# balancer.net
KiCad netlist of a schematic drawn in EAGLE
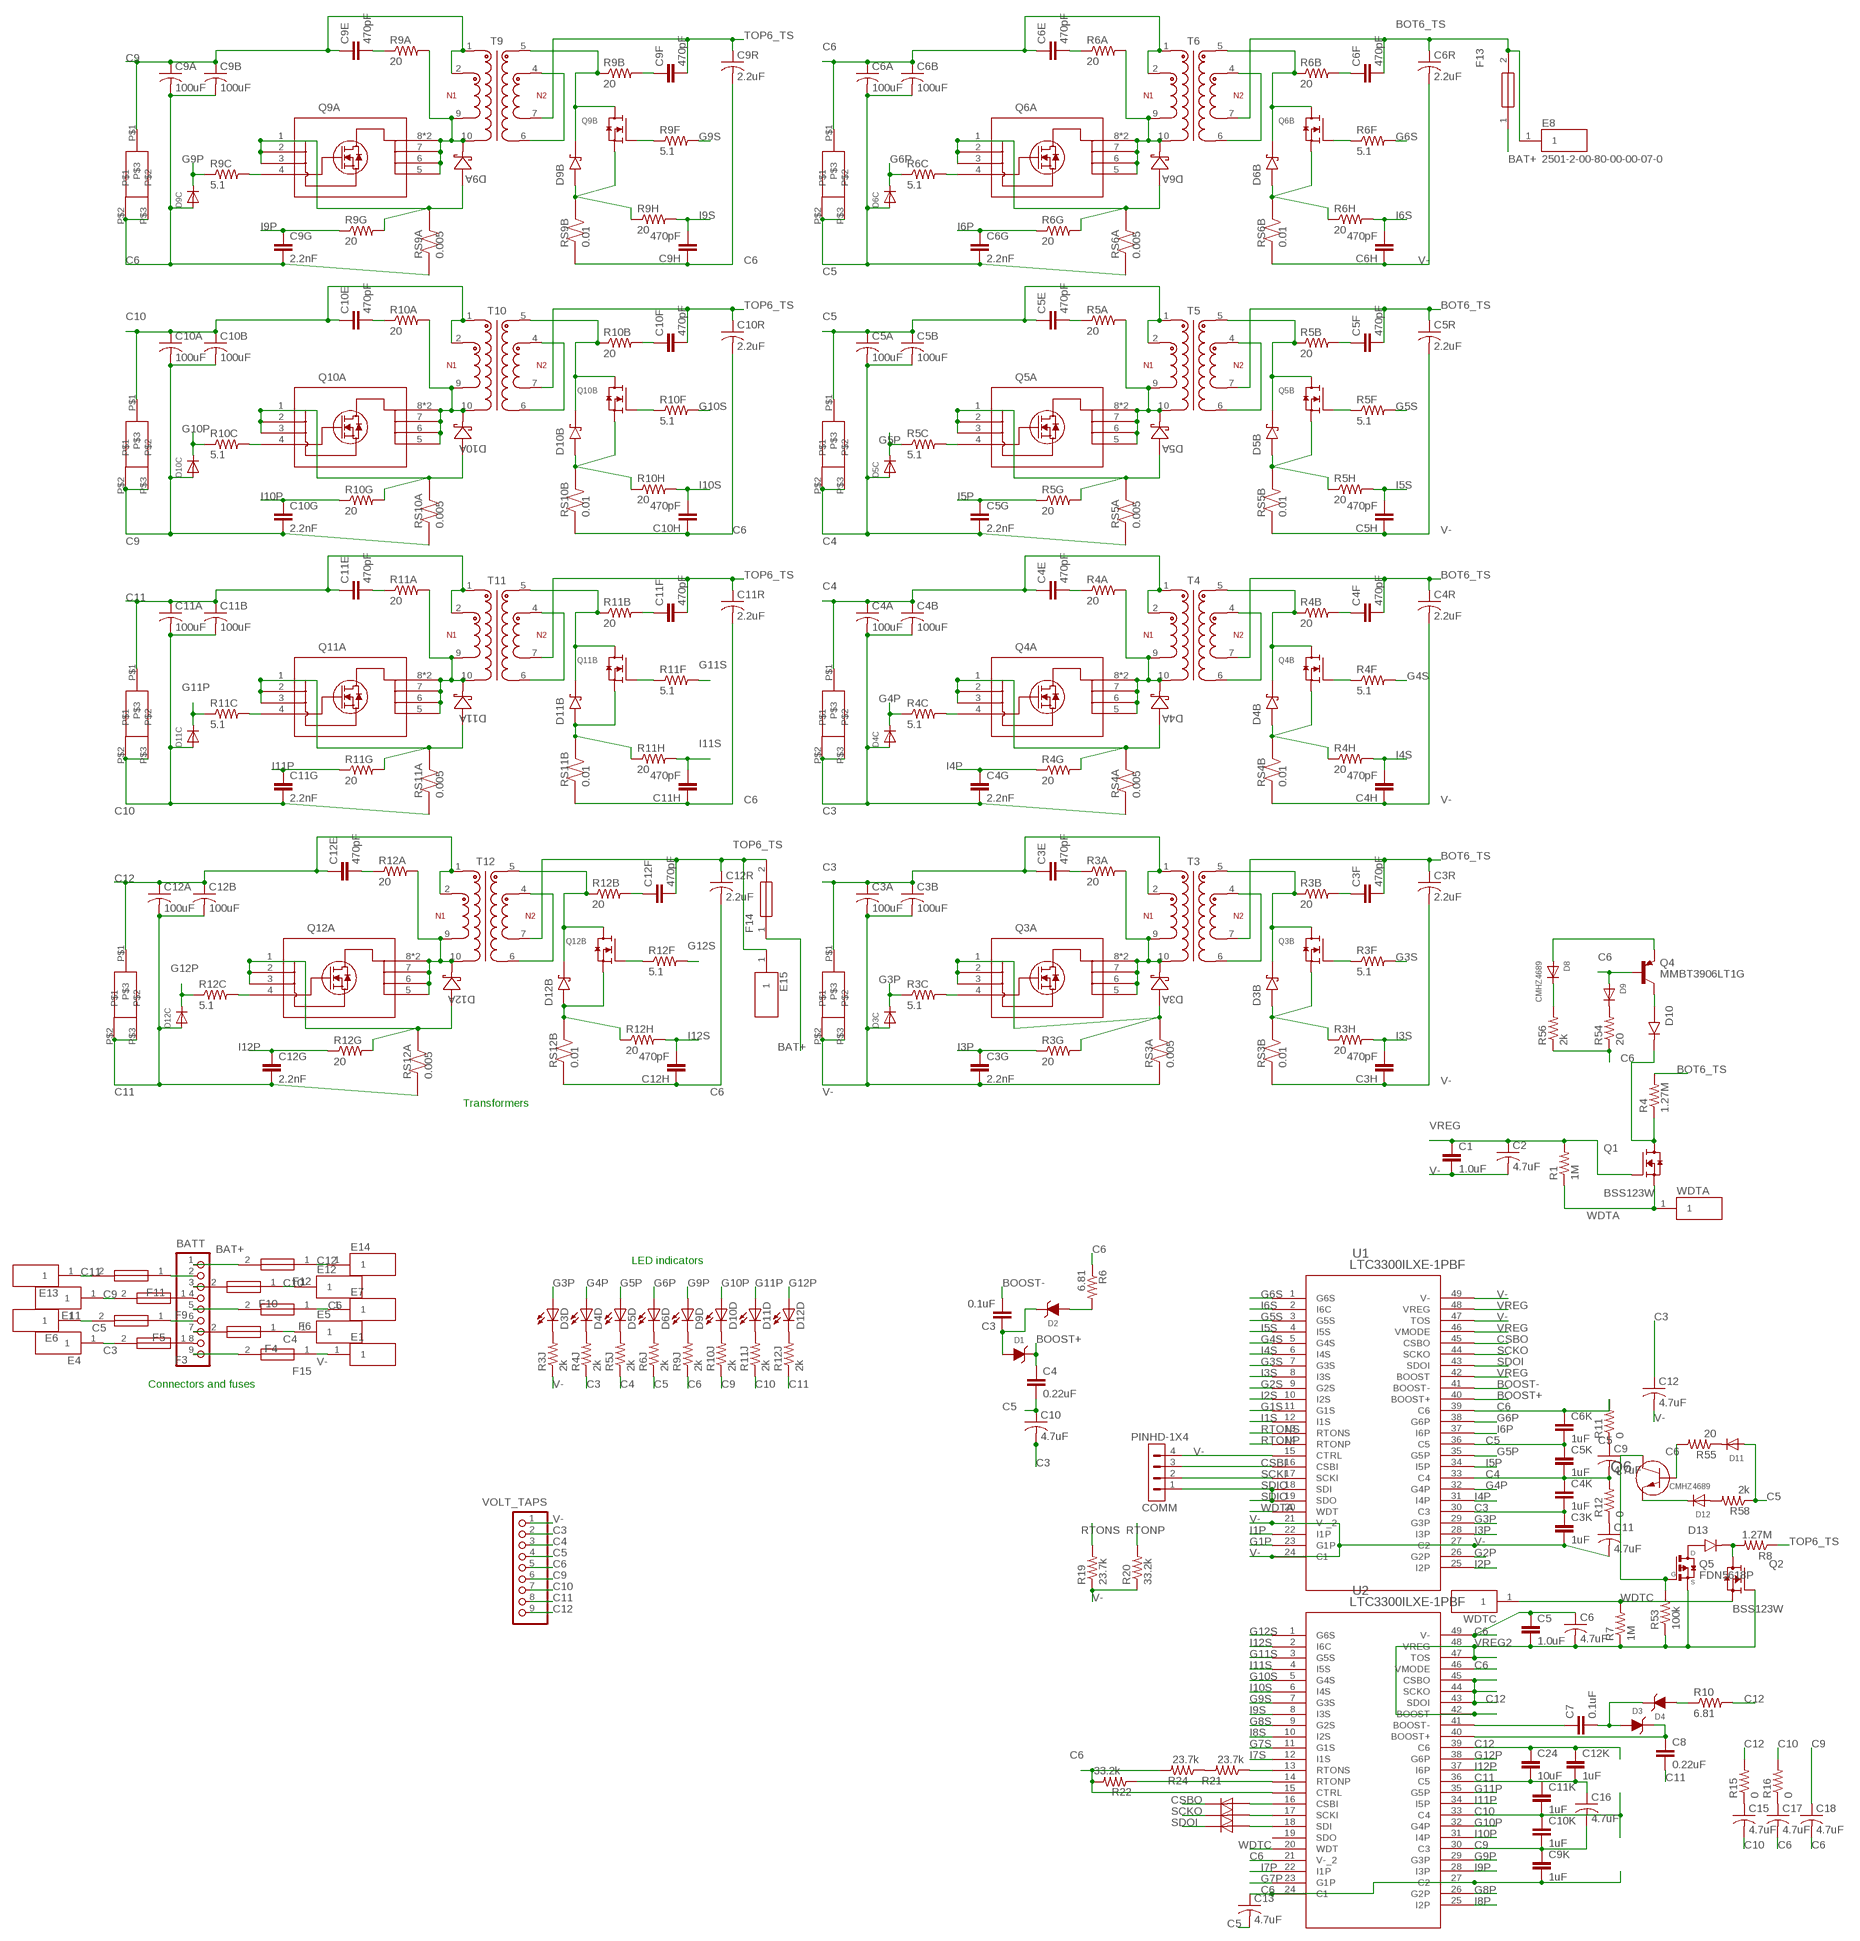
[diagram p0: schematic, sheet 1]

(export (version "E")
  (design (tool "Eeschema 10.0.6"))
  (components
    (comp (ref "BATT")
      (value "B9P-VH")
      (footprint "eagle-import:B9P-VH")
      (libsource (lib "eagle-import") (part "B9P-VH"))
    )
    (comp (ref "C1")
      (value "1.0uF")
      (footprint "eagle-import:0805")
      (libsource (lib "eagle-import") (part "CAP"))
    )
    (comp (ref "C2")
      (value "4.7uF")
      (footprint "eagle-import:C1210")
      (libsource (lib "eagle-import") (part "C-USC1210"))
    )
    (comp (ref "C3")
      (value "0.1uF")
      (footprint "eagle-import:0805")
      (libsource (lib "eagle-import") (part "CAP"))
    )
    (comp (ref "C3A")
      (value "100uF")
      (footprint "eagle-import:C1210")
      (libsource (lib "eagle-import") (part "C-USC1210"))
    )
    (comp (ref "C3B")
      (value "100uF")
      (footprint "eagle-import:C1210")
      (libsource (lib "eagle-import") (part "C-USC1210"))
    )
    (comp (ref "C3E")
      (value "470pF")
      (footprint "eagle-import:0805")
      (libsource (lib "eagle-import") (part "CAP"))
    )
    (comp (ref "C3F")
      (value "470pF")
      (footprint "eagle-import:0805")
      (libsource (lib "eagle-import") (part "CAP"))
    )
    (comp (ref "C3G")
      (value "2.2nF")
      (footprint "eagle-import:0805")
      (libsource (lib "eagle-import") (part "CAP"))
    )
    (comp (ref "C3H")
      (value "470pF")
      (footprint "eagle-import:0805")
      (libsource (lib "eagle-import") (part "CAP"))
    )
    (comp (ref "C3K")
      (value "1uF")
      (footprint "eagle-import:0805")
      (libsource (lib "eagle-import") (part "CAP"))
    )
    (comp (ref "C3R")
      (value "2.2uF")
      (footprint "eagle-import:C1210")
      (libsource (lib "eagle-import") (part "C-USC1210"))
    )
    (comp (ref "C4")
      (value "0.22uF")
      (footprint "eagle-import:0805")
      (libsource (lib "eagle-import") (part "CAP"))
    )
    (comp (ref "C4A")
      (value "100uF")
      (footprint "eagle-import:C1210")
      (libsource (lib "eagle-import") (part "C-USC1210"))
    )
    (comp (ref "C4B")
      (value "100uF")
      (footprint "eagle-import:C1210")
      (libsource (lib "eagle-import") (part "C-USC1210"))
    )
    (comp (ref "C4E")
      (value "470pF")
      (footprint "eagle-import:0805")
      (libsource (lib "eagle-import") (part "CAP"))
    )
    (comp (ref "C4F")
      (value "470pF")
      (footprint "eagle-import:0805")
      (libsource (lib "eagle-import") (part "CAP"))
    )
    (comp (ref "C4G")
      (value "2.2nF")
      (footprint "eagle-import:0805")
      (libsource (lib "eagle-import") (part "CAP"))
    )
    (comp (ref "C4H")
      (value "470pF")
      (footprint "eagle-import:0805")
      (libsource (lib "eagle-import") (part "CAP"))
    )
    (comp (ref "C4K")
      (value "1uF")
      (footprint "eagle-import:0805")
      (libsource (lib "eagle-import") (part "CAP"))
    )
    (comp (ref "C4R")
      (value "2.2uF")
      (footprint "eagle-import:C1210")
      (libsource (lib "eagle-import") (part "C-USC1210"))
    )
    (comp (ref "C5")
      (value "1.0uF")
      (footprint "eagle-import:0805")
      (libsource (lib "eagle-import") (part "CAP"))
    )
    (comp (ref "C5A")
      (value "100uF")
      (footprint "eagle-import:C1210")
      (libsource (lib "eagle-import") (part "C-USC1210"))
    )
    (comp (ref "C5B")
      (value "100uF")
      (footprint "eagle-import:C1210")
      (libsource (lib "eagle-import") (part "C-USC1210"))
    )
    (comp (ref "C5E")
      (value "470pF")
      (footprint "eagle-import:0805")
      (libsource (lib "eagle-import") (part "CAP"))
    )
    (comp (ref "C5F")
      (value "470pF")
      (footprint "eagle-import:0805")
      (libsource (lib "eagle-import") (part "CAP"))
    )
    (comp (ref "C5G")
      (value "2.2nF")
      (footprint "eagle-import:0805")
      (libsource (lib "eagle-import") (part "CAP"))
    )
    (comp (ref "C5H")
      (value "470pF")
      (footprint "eagle-import:0805")
      (libsource (lib "eagle-import") (part "CAP"))
    )
    (comp (ref "C5K")
      (value "1uF")
      (footprint "eagle-import:0805")
      (libsource (lib "eagle-import") (part "CAP"))
    )
    (comp (ref "C5R")
      (value "2.2uF")
      (footprint "eagle-import:C1210")
      (libsource (lib "eagle-import") (part "C-USC1210"))
    )
    (comp (ref "C6")
      (value "4.7uF")
      (footprint "eagle-import:C1210")
      (libsource (lib "eagle-import") (part "C-USC1210"))
    )
    (comp (ref "C6A")
      (value "100uF")
      (footprint "eagle-import:C1210")
      (libsource (lib "eagle-import") (part "C-USC1210"))
    )
    (comp (ref "C6B")
      (value "100uF")
      (footprint "eagle-import:C1210")
      (libsource (lib "eagle-import") (part "C-USC1210"))
    )
    (comp (ref "C6E")
      (value "470pF")
      (footprint "eagle-import:0805")
      (libsource (lib "eagle-import") (part "CAP"))
    )
    (comp (ref "C6F")
      (value "470pF")
      (footprint "eagle-import:0805")
      (libsource (lib "eagle-import") (part "CAP"))
    )
    (comp (ref "C6G")
      (value "2.2nF")
      (footprint "eagle-import:0805")
      (libsource (lib "eagle-import") (part "CAP"))
    )
    (comp (ref "C6H")
      (value "470pF")
      (footprint "eagle-import:0805")
      (libsource (lib "eagle-import") (part "CAP"))
    )
    (comp (ref "C6K")
      (value "1uF")
      (footprint "eagle-import:0805")
      (libsource (lib "eagle-import") (part "CAP"))
    )
    (comp (ref "C6R")
      (value "2.2uF")
      (footprint "eagle-import:C1210")
      (libsource (lib "eagle-import") (part "C-USC1210"))
    )
    (comp (ref "C7")
      (value "0.1uF")
      (footprint "eagle-import:0805")
      (libsource (lib "eagle-import") (part "CAP"))
    )
    (comp (ref "C8")
      (value "0.22uF")
      (footprint "eagle-import:0805")
      (libsource (lib "eagle-import") (part "CAP"))
    )
    (comp (ref "C9")
      (value "4.7uF")
      (footprint "eagle-import:C1210")
      (libsource (lib "eagle-import") (part "C-USC1210"))
    )
    (comp (ref "C9A")
      (value "100uF")
      (footprint "eagle-import:C1210")
      (libsource (lib "eagle-import") (part "C-USC1210"))
    )
    (comp (ref "C9B")
      (value "100uF")
      (footprint "eagle-import:C1210")
      (libsource (lib "eagle-import") (part "C-USC1210"))
    )
    (comp (ref "C9E")
      (value "470pF")
      (footprint "eagle-import:0805")
      (libsource (lib "eagle-import") (part "CAP"))
    )
    (comp (ref "C9F")
      (value "470pF")
      (footprint "eagle-import:0805")
      (libsource (lib "eagle-import") (part "CAP"))
    )
    (comp (ref "C9G")
      (value "2.2nF")
      (footprint "eagle-import:0805")
      (libsource (lib "eagle-import") (part "CAP"))
    )
    (comp (ref "C9H")
      (value "470pF")
      (footprint "eagle-import:0805")
      (libsource (lib "eagle-import") (part "CAP"))
    )
    (comp (ref "C9K")
      (value "1uF")
      (footprint "eagle-import:0805")
      (libsource (lib "eagle-import") (part "CAP"))
    )
    (comp (ref "C9R")
      (value "2.2uF")
      (footprint "eagle-import:C1210")
      (libsource (lib "eagle-import") (part "C-USC1210"))
    )
    (comp (ref "C10")
      (value "4.7uF")
      (footprint "eagle-import:C1210")
      (libsource (lib "eagle-import") (part "C-USC1210"))
    )
    (comp (ref "C10A")
      (value "100uF")
      (footprint "eagle-import:C1210")
      (libsource (lib "eagle-import") (part "C-USC1210"))
    )
    (comp (ref "C10B")
      (value "100uF")
      (footprint "eagle-import:C1210")
      (libsource (lib "eagle-import") (part "C-USC1210"))
    )
    (comp (ref "C10E")
      (value "470pF")
      (footprint "eagle-import:0805")
      (libsource (lib "eagle-import") (part "CAP"))
    )
    (comp (ref "C10F")
      (value "470pF")
      (footprint "eagle-import:0805")
      (libsource (lib "eagle-import") (part "CAP"))
    )
    (comp (ref "C10G")
      (value "2.2nF")
      (footprint "eagle-import:0805")
      (libsource (lib "eagle-import") (part "CAP"))
    )
    (comp (ref "C10H")
      (value "470pF")
      (footprint "eagle-import:0805")
      (libsource (lib "eagle-import") (part "CAP"))
    )
    (comp (ref "C10K")
      (value "1uF")
      (footprint "eagle-import:0805")
      (libsource (lib "eagle-import") (part "CAP"))
    )
    (comp (ref "C10R")
      (value "2.2uF")
      (footprint "eagle-import:C1210")
      (libsource (lib "eagle-import") (part "C-USC1210"))
    )
    (comp (ref "C11")
      (value "4.7uF")
      (footprint "eagle-import:C1210")
      (libsource (lib "eagle-import") (part "C-USC1210"))
    )
    (comp (ref "C11A")
      (value "100uF")
      (footprint "eagle-import:C1210")
      (libsource (lib "eagle-import") (part "C-USC1210"))
    )
    (comp (ref "C11B")
      (value "100uF")
      (footprint "eagle-import:C1210")
      (libsource (lib "eagle-import") (part "C-USC1210"))
    )
    (comp (ref "C11E")
      (value "470pF")
      (footprint "eagle-import:0805")
      (libsource (lib "eagle-import") (part "CAP"))
    )
    (comp (ref "C11F")
      (value "470pF")
      (footprint "eagle-import:0805")
      (libsource (lib "eagle-import") (part "CAP"))
    )
    (comp (ref "C11G")
      (value "2.2nF")
      (footprint "eagle-import:0805")
      (libsource (lib "eagle-import") (part "CAP"))
    )
    (comp (ref "C11H")
      (value "470pF")
      (footprint "eagle-import:0805")
      (libsource (lib "eagle-import") (part "CAP"))
    )
    (comp (ref "C11K")
      (value "1uF")
      (footprint "eagle-import:0805")
      (libsource (lib "eagle-import") (part "CAP"))
    )
    (comp (ref "C11R")
      (value "2.2uF")
      (footprint "eagle-import:C1210")
      (libsource (lib "eagle-import") (part "C-USC1210"))
    )
    (comp (ref "C12")
      (value "4.7uF")
      (footprint "eagle-import:C1210")
      (libsource (lib "eagle-import") (part "C-USC1210"))
    )
    (comp (ref "C12A")
      (value "100uF")
      (footprint "eagle-import:C1210")
      (libsource (lib "eagle-import") (part "C-USC1210"))
    )
    (comp (ref "C12B")
      (value "100uF")
      (footprint "eagle-import:C1210")
      (libsource (lib "eagle-import") (part "C-USC1210"))
    )
    (comp (ref "C12E")
      (value "470pF")
      (footprint "eagle-import:0805")
      (libsource (lib "eagle-import") (part "CAP"))
    )
    (comp (ref "C12F")
      (value "470pF")
      (footprint "eagle-import:0805")
      (libsource (lib "eagle-import") (part "CAP"))
    )
    (comp (ref "C12G")
      (value "2.2nF")
      (footprint "eagle-import:0805")
      (libsource (lib "eagle-import") (part "CAP"))
    )
    (comp (ref "C12H")
      (value "470pF")
      (footprint "eagle-import:0805")
      (libsource (lib "eagle-import") (part "CAP"))
    )
    (comp (ref "C12K")
      (value "1uF")
      (footprint "eagle-import:0805")
      (libsource (lib "eagle-import") (part "CAP"))
    )
    (comp (ref "C12R")
      (value "2.2uF")
      (footprint "eagle-import:C1210")
      (libsource (lib "eagle-import") (part "C-USC1210"))
    )
    (comp (ref "C13")
      (value "4.7uF")
      (footprint "eagle-import:C1210")
      (libsource (lib "eagle-import") (part "C-USC1210"))
    )
    (comp (ref "C15")
      (value "4.7uF")
      (footprint "eagle-import:C1210")
      (libsource (lib "eagle-import") (part "C-USC1210"))
    )
    (comp (ref "C16")
      (value "4.7uF")
      (footprint "eagle-import:C1210")
      (libsource (lib "eagle-import") (part "C-USC1210"))
    )
    (comp (ref "C17")
      (value "4.7uF")
      (footprint "eagle-import:C1210")
      (libsource (lib "eagle-import") (part "C-USC1210"))
    )
    (comp (ref "C18")
      (value "4.7uF")
      (footprint "eagle-import:C1210")
      (libsource (lib "eagle-import") (part "C-USC1210"))
    )
    (comp (ref "C24")
      (value "10uF")
      (footprint "eagle-import:0805")
      (libsource (lib "eagle-import") (part "CAP"))
    )
    (comp (ref "COMM")
      (value "PINHD-1X4")
      (footprint "eagle-import:1X04")
      (libsource (lib "eagle-import") (part "PINHD-1X4"))
    )
    (comp (ref "D1")
      (value "WE-TVSP_DO-214AA_600W_UNI")
      (footprint "eagle-import:WE-TVSP_DO-214AA_UNIDIRECTIONAL")
      (fields (field (name "MF") "Würth Elektronik") (field (name "MP") "824520141"))
      (libsource (lib "eagle-import") (part "WE-TVSP_DO-214AA_600W_UNI"))
    )
    (comp (ref "D2")
      (value "WE-TVSP_DO-214AA_600W_UNI")
      (footprint "eagle-import:WE-TVSP_DO-214AA_UNIDIRECTIONAL")
      (fields (field (name "MF") "Würth Elektronik") (field (name "MP") "824520141"))
      (libsource (lib "eagle-import") (part "WE-TVSP_DO-214AA_600W_UNI"))
    )
    (comp (ref "D3")
      (value "WE-TVSP_DO-214AA_600W_UNI")
      (footprint "eagle-import:WE-TVSP_DO-214AA_UNIDIRECTIONAL")
      (fields (field (name "MF") "Würth Elektronik") (field (name "MP") "824520141"))
      (libsource (lib "eagle-import") (part "WE-TVSP_DO-214AA_600W_UNI"))
    )
    (comp (ref "D3A")
      (value "DFLS260Q-7")
      (footprint "eagle-import:SDO_POWERDI123_DIO")
      (fields (field (name "COPYRIGHT") "Copyright (C) 2026 Ultra Librarian. All rights reserved."))
      (libsource (lib "eagle-import") (part "DFLS260Q-7"))
    )
    (comp (ref "D3B")
      (value "DFLS1100-7")
      (footprint "eagle-import:DIO_DFLS1100-7")
      (fields (field (name "MANUFACTURER") "Diodes Inc."))
      (libsource (lib "eagle-import") (part "DFLS1100-7"))
    )
    (comp (ref "D3C")
      (value "DIODESOD-523")
      (footprint "eagle-import:SOD-523")
      (libsource (lib "eagle-import") (part "DIODESOD-523"))
    )
    (comp (ref "D3D")
      (value "LEDCHIPLED_0805")
      (footprint "eagle-import:CHIPLED_0805")
      (libsource (lib "eagle-import") (part "LEDCHIPLED_0805"))
    )
    (comp (ref "D3E")
      (value "SBR10U200P5")
      (footprint "eagle-import:POWERDI5")
      (libsource (lib "eagle-import") (part "SBR10U200P5"))
    )
    (comp (ref "D4")
      (value "WE-TVSP_DO-214AA_600W_UNI")
      (footprint "eagle-import:WE-TVSP_DO-214AA_UNIDIRECTIONAL")
      (fields (field (name "MF") "Würth Elektronik") (field (name "MP") "824520141"))
      (libsource (lib "eagle-import") (part "WE-TVSP_DO-214AA_600W_UNI"))
    )
    (comp (ref "D4A")
      (value "DFLS260Q-7")
      (footprint "eagle-import:SDO_POWERDI123_DIO")
      (fields (field (name "COPYRIGHT") "Copyright (C) 2026 Ultra Librarian. All rights reserved."))
      (libsource (lib "eagle-import") (part "DFLS260Q-7"))
    )
    (comp (ref "D4B")
      (value "DFLS1100-7")
      (footprint "eagle-import:DIO_DFLS1100-7")
      (fields (field (name "MANUFACTURER") "Diodes Inc."))
      (libsource (lib "eagle-import") (part "DFLS1100-7"))
    )
    (comp (ref "D4C")
      (value "DIODESOD-523")
      (footprint "eagle-import:SOD-523")
      (libsource (lib "eagle-import") (part "DIODESOD-523"))
    )
    (comp (ref "D4D")
      (value "LEDCHIPLED_0805")
      (footprint "eagle-import:CHIPLED_0805")
      (libsource (lib "eagle-import") (part "LEDCHIPLED_0805"))
    )
    (comp (ref "D4E")
      (value "SBR10U200P5")
      (footprint "eagle-import:POWERDI5")
      (libsource (lib "eagle-import") (part "SBR10U200P5"))
    )
    (comp (ref "D5")
      (value "RS07J-GS18")
      (footprint "eagle-import:SODFL3718X108N")
      (fields (field (name "MF") "Vishay Semiconductor"))
      (libsource (lib "eagle-import") (part "RS07J-GS18"))
    )
    (comp (ref "D5A")
      (value "DFLS260Q-7")
      (footprint "eagle-import:SDO_POWERDI123_DIO")
      (fields (field (name "COPYRIGHT") "Copyright (C) 2026 Ultra Librarian. All rights reserved."))
      (libsource (lib "eagle-import") (part "DFLS260Q-7"))
    )
    (comp (ref "D5B")
      (value "DFLS1100-7")
      (footprint "eagle-import:DIO_DFLS1100-7")
      (fields (field (name "MANUFACTURER") "Diodes Inc."))
      (libsource (lib "eagle-import") (part "DFLS1100-7"))
    )
    (comp (ref "D5C")
      (value "DIODESOD-523")
      (footprint "eagle-import:SOD-523")
      (libsource (lib "eagle-import") (part "DIODESOD-523"))
    )
    (comp (ref "D5D")
      (value "LEDCHIPLED_0805")
      (footprint "eagle-import:CHIPLED_0805")
      (libsource (lib "eagle-import") (part "LEDCHIPLED_0805"))
    )
    (comp (ref "D5E")
      (value "SBR10U200P5")
      (footprint "eagle-import:POWERDI5")
      (libsource (lib "eagle-import") (part "SBR10U200P5"))
    )
    (comp (ref "D6")
      (value "RS07J-GS18")
      (footprint "eagle-import:SODFL3718X108N")
      (fields (field (name "MF") "Vishay Semiconductor"))
      (libsource (lib "eagle-import") (part "RS07J-GS18"))
    )
    (comp (ref "D6A")
      (value "DFLS260Q-7")
      (footprint "eagle-import:SDO_POWERDI123_DIO")
      (fields (field (name "COPYRIGHT") "Copyright (C) 2026 Ultra Librarian. All rights reserved."))
      (libsource (lib "eagle-import") (part "DFLS260Q-7"))
    )
    (comp (ref "D6B")
      (value "DFLS1100-7")
      (footprint "eagle-import:DIO_DFLS1100-7")
      (fields (field (name "MANUFACTURER") "Diodes Inc."))
      (libsource (lib "eagle-import") (part "DFLS1100-7"))
    )
    (comp (ref "D6C")
      (value "DIODESOD-523")
      (footprint "eagle-import:SOD-523")
      (libsource (lib "eagle-import") (part "DIODESOD-523"))
    )
    (comp (ref "D6D")
      (value "LEDCHIPLED_0805")
      (footprint "eagle-import:CHIPLED_0805")
      (libsource (lib "eagle-import") (part "LEDCHIPLED_0805"))
    )
    (comp (ref "D6E")
      (value "SBR10U200P5")
      (footprint "eagle-import:POWERDI5")
      (libsource (lib "eagle-import") (part "SBR10U200P5"))
    )
    (comp (ref "D7")
      (value "RS07J-GS18")
      (footprint "eagle-import:SODFL3718X108N")
      (fields (field (name "MF") "Vishay Semiconductor"))
      (libsource (lib "eagle-import") (part "RS07J-GS18"))
    )
    (comp (ref "D8")
      (value "CMHZ4689")
      (footprint "eagle-import:SOD-123")
      (libsource (lib "eagle-import") (part "DIODESOD-123"))
    )
    (comp (ref "D9")
      (value "PDZ5.6B")
      (footprint "eagle-import:SOD-323F")
      (libsource (lib "eagle-import") (part "DIODESOD-323F"))
    )
    (comp (ref "D9A")
      (value "DFLS260Q-7")
      (footprint "eagle-import:SDO_POWERDI123_DIO")
      (fields (field (name "COPYRIGHT") "Copyright (C) 2026 Ultra Librarian. All rights reserved."))
      (libsource (lib "eagle-import") (part "DFLS260Q-7"))
    )
    (comp (ref "D9B")
      (value "DFLS1100-7")
      (footprint "eagle-import:DIO_DFLS1100-7")
      (fields (field (name "MANUFACTURER") "Diodes Inc."))
      (libsource (lib "eagle-import") (part "DFLS1100-7"))
    )
    (comp (ref "D9C")
      (value "DIODESOD-523")
      (footprint "eagle-import:SOD-523")
      (libsource (lib "eagle-import") (part "DIODESOD-523"))
    )
    (comp (ref "D9D")
      (value "LEDCHIPLED_0805")
      (footprint "eagle-import:CHIPLED_0805")
      (libsource (lib "eagle-import") (part "LEDCHIPLED_0805"))
    )
    (comp (ref "D9E")
      (value "SBR10U200P5")
      (footprint "eagle-import:POWERDI5")
      (libsource (lib "eagle-import") (part "SBR10U200P5"))
    )
    (comp (ref "D10")
      (value "1N4448HWT-7")
      (footprint "eagle-import:SODFL1608X65N")
      (fields (field (name "MF") "Diodes Inc."))
      (libsource (lib "eagle-import") (part "1N4448HWT-7"))
    )
    (comp (ref "D10A")
      (value "DFLS260Q-7")
      (footprint "eagle-import:SDO_POWERDI123_DIO")
      (fields (field (name "COPYRIGHT") "Copyright (C) 2026 Ultra Librarian. All rights reserved."))
      (libsource (lib "eagle-import") (part "DFLS260Q-7"))
    )
    (comp (ref "D10B")
      (value "DFLS1100-7")
      (footprint "eagle-import:DIO_DFLS1100-7")
      (fields (field (name "MANUFACTURER") "Diodes Inc."))
      (libsource (lib "eagle-import") (part "DFLS1100-7"))
    )
    (comp (ref "D10C")
      (value "DIODESOD-523")
      (footprint "eagle-import:SOD-523")
      (libsource (lib "eagle-import") (part "DIODESOD-523"))
    )
    (comp (ref "D10D")
      (value "LEDCHIPLED_0805")
      (footprint "eagle-import:CHIPLED_0805")
      (libsource (lib "eagle-import") (part "LEDCHIPLED_0805"))
    )
    (comp (ref "D10E")
      (value "SBR10U200P5")
      (footprint "eagle-import:POWERDI5")
      (libsource (lib "eagle-import") (part "SBR10U200P5"))
    )
    (comp (ref "D11")
      (value "PDZ5.6B")
      (footprint "eagle-import:SOD-323F")
      (libsource (lib "eagle-import") (part "DIODESOD-323F"))
    )
    (comp (ref "D11A")
      (value "DFLS260Q-7")
      (footprint "eagle-import:SDO_POWERDI123_DIO")
      (fields (field (name "COPYRIGHT") "Copyright (C) 2026 Ultra Librarian. All rights reserved."))
      (libsource (lib "eagle-import") (part "DFLS260Q-7"))
    )
    (comp (ref "D11B")
      (value "DFLS1100-7")
      (footprint "eagle-import:DIO_DFLS1100-7")
      (fields (field (name "MANUFACTURER") "Diodes Inc."))
      (libsource (lib "eagle-import") (part "DFLS1100-7"))
    )
    (comp (ref "D11C")
      (value "DIODESOD-523")
      (footprint "eagle-import:SOD-523")
      (libsource (lib "eagle-import") (part "DIODESOD-523"))
    )
    (comp (ref "D11D")
      (value "LEDCHIPLED_0805")
      (footprint "eagle-import:CHIPLED_0805")
      (libsource (lib "eagle-import") (part "LEDCHIPLED_0805"))
    )
    (comp (ref "D11E")
      (value "SBR10U200P5")
      (footprint "eagle-import:POWERDI5")
      (libsource (lib "eagle-import") (part "SBR10U200P5"))
    )
    (comp (ref "D12")
      (value "CMHZ4689")
      (footprint "eagle-import:SOD-123")
      (libsource (lib "eagle-import") (part "DIODESOD-123"))
    )
    (comp (ref "D12A")
      (value "DFLS260Q-7")
      (footprint "eagle-import:SDO_POWERDI123_DIO")
      (fields (field (name "COPYRIGHT") "Copyright (C) 2026 Ultra Librarian. All rights reserved."))
      (libsource (lib "eagle-import") (part "DFLS260Q-7"))
    )
    (comp (ref "D12B")
      (value "DFLS1100-7")
      (footprint "eagle-import:DIO_DFLS1100-7")
      (fields (field (name "MANUFACTURER") "Diodes Inc."))
      (libsource (lib "eagle-import") (part "DFLS1100-7"))
    )
    (comp (ref "D12C")
      (value "DIODESOD-523")
      (footprint "eagle-import:SOD-523")
      (libsource (lib "eagle-import") (part "DIODESOD-523"))
    )
    (comp (ref "D12D")
      (value "LEDCHIPLED_0805")
      (footprint "eagle-import:CHIPLED_0805")
      (libsource (lib "eagle-import") (part "LEDCHIPLED_0805"))
    )
    (comp (ref "D12E")
      (value "SBR10U200P5")
      (footprint "eagle-import:POWERDI5")
      (libsource (lib "eagle-import") (part "SBR10U200P5"))
    )
    (comp (ref "D13")
      (value "1N4448HWT-7")
      (footprint "eagle-import:SODFL1608X65N")
      (fields (field (name "MF") "Diodes Inc."))
      (libsource (lib "eagle-import") (part "1N4448HWT-7"))
    )
    (comp (ref "E1")
      (value "2501-2-00-80-00-00-07-0")
      (footprint "eagle-import:MILMAX_2501-2-00-80-00-00-07-0")
      (fields (field (name "MANUFACTURER") "MILMAX"))
      (libsource (lib "eagle-import") (part "2501-2-00-80-00-00-07-0"))
    )
    (comp (ref "E4")
      (value "2501-2-00-80-00-00-07-0")
      (footprint "eagle-import:MILMAX_2501-2-00-80-00-00-07-0")
      (fields (field (name "MANUFACTURER") "MILMAX"))
      (libsource (lib "eagle-import") (part "2501-2-00-80-00-00-07-0"))
    )
    (comp (ref "E5")
      (value "2501-2-00-80-00-00-07-0")
      (footprint "eagle-import:MILMAX_2501-2-00-80-00-00-07-0")
      (fields (field (name "MANUFACTURER") "MILMAX"))
      (libsource (lib "eagle-import") (part "2501-2-00-80-00-00-07-0"))
    )
    (comp (ref "E6")
      (value "2501-2-00-80-00-00-07-0")
      (footprint "eagle-import:MILMAX_2501-2-00-80-00-00-07-0")
      (fields (field (name "MANUFACTURER") "MILMAX"))
      (libsource (lib "eagle-import") (part "2501-2-00-80-00-00-07-0"))
    )
    (comp (ref "E7")
      (value "2501-2-00-80-00-00-07-0")
      (footprint "eagle-import:MILMAX_2501-2-00-80-00-00-07-0")
      (fields (field (name "MANUFACTURER") "MILMAX"))
      (libsource (lib "eagle-import") (part "2501-2-00-80-00-00-07-0"))
    )
    (comp (ref "E8")
      (value "2501-2-00-80-00-00-07-0")
      (footprint "eagle-import:MILMAX_2501-2-00-80-00-00-07-0")
      (fields (field (name "MANUFACTURER") "MILMAX"))
      (libsource (lib "eagle-import") (part "2501-2-00-80-00-00-07-0"))
    )
    (comp (ref "E11")
      (value "2501-2-00-80-00-00-07-0")
      (footprint "eagle-import:MILMAX_2501-2-00-80-00-00-07-0")
      (fields (field (name "MANUFACTURER") "MILMAX"))
      (libsource (lib "eagle-import") (part "2501-2-00-80-00-00-07-0"))
    )
    (comp (ref "E12")
      (value "2501-2-00-80-00-00-07-0")
      (footprint "eagle-import:MILMAX_2501-2-00-80-00-00-07-0")
      (fields (field (name "MANUFACTURER") "MILMAX"))
      (libsource (lib "eagle-import") (part "2501-2-00-80-00-00-07-0"))
    )
    (comp (ref "E13")
      (value "2501-2-00-80-00-00-07-0")
      (footprint "eagle-import:MILMAX_2501-2-00-80-00-00-07-0")
      (fields (field (name "MANUFACTURER") "MILMAX"))
      (libsource (lib "eagle-import") (part "2501-2-00-80-00-00-07-0"))
    )
    (comp (ref "E14")
      (value "2501-2-00-80-00-00-07-0")
      (footprint "eagle-import:MILMAX_2501-2-00-80-00-00-07-0")
      (fields (field (name "MANUFACTURER") "MILMAX"))
      (libsource (lib "eagle-import") (part "2501-2-00-80-00-00-07-0"))
    )
    (comp (ref "E15")
      (value "2501-2-00-80-00-00-07-0")
      (footprint "eagle-import:MILMAX_2501-2-00-80-00-00-07-0")
      (fields (field (name "MANUFACTURER") "MILMAX"))
      (libsource (lib "eagle-import") (part "2501-2-00-80-00-00-07-0"))
    )
    (comp (ref "F3")
      (value "01530008Z")
      (footprint "eagle-import:01530008")
      (fields (field (name "MF") "Littelfuse Inc."))
      (libsource (lib "eagle-import") (part "01530008Z"))
    )
    (comp (ref "F4")
      (value "01530008Z")
      (footprint "eagle-import:01530008")
      (fields (field (name "MF") "Littelfuse Inc."))
      (libsource (lib "eagle-import") (part "01530008Z"))
    )
    (comp (ref "F5")
      (value "01530008Z")
      (footprint "eagle-import:01530008")
      (fields (field (name "MF") "Littelfuse Inc."))
      (libsource (lib "eagle-import") (part "01530008Z"))
    )
    (comp (ref "F6")
      (value "01530008Z")
      (footprint "eagle-import:01530008")
      (fields (field (name "MF") "Littelfuse Inc."))
      (libsource (lib "eagle-import") (part "01530008Z"))
    )
    (comp (ref "F9")
      (value "01530008Z")
      (footprint "eagle-import:01530008")
      (fields (field (name "MF") "Littelfuse Inc."))
      (libsource (lib "eagle-import") (part "01530008Z"))
    )
    (comp (ref "F10")
      (value "01530008Z")
      (footprint "eagle-import:01530008")
      (fields (field (name "MF") "Littelfuse Inc."))
      (libsource (lib "eagle-import") (part "01530008Z"))
    )
    (comp (ref "F11")
      (value "01530008Z")
      (footprint "eagle-import:01530008")
      (fields (field (name "MF") "Littelfuse Inc."))
      (libsource (lib "eagle-import") (part "01530008Z"))
    )
    (comp (ref "F12")
      (value "01530008Z")
      (footprint "eagle-import:01530008")
      (fields (field (name "MF") "Littelfuse Inc."))
      (libsource (lib "eagle-import") (part "01530008Z"))
    )
    (comp (ref "F13")
      (value "01530008Z")
      (footprint "eagle-import:01530008")
      (fields (field (name "MF") "Littelfuse Inc."))
      (libsource (lib "eagle-import") (part "01530008Z"))
    )
    (comp (ref "F14")
      (value "01530008Z")
      (footprint "eagle-import:01530008")
      (fields (field (name "MF") "Littelfuse Inc."))
      (libsource (lib "eagle-import") (part "01530008Z"))
    )
    (comp (ref "F15")
      (value "01530008Z")
      (footprint "eagle-import:01530008")
      (fields (field (name "MF") "Littelfuse Inc."))
      (libsource (lib "eagle-import") (part "01530008Z"))
    )
    (comp (ref "Q1")
      (value "BSS123W")
      (footprint "eagle-import:TRANS_BSS123W")
      (fields (field (name "MF") "Taiwan Semiconductor Corporation"))
      (libsource (lib "eagle-import") (part "BSS123W"))
    )
    (comp (ref "Q2")
      (value "BSS123W")
      (footprint "eagle-import:TRANS_BSS123W")
      (fields (field (name "MF") "Taiwan Semiconductor Corporation"))
      (libsource (lib "eagle-import") (part "BSS123W"))
    )
    (comp (ref "Q3A")
      (value "SIR882DP-T1-GE3")
      (footprint "eagle-import:POWERPAK_SO-8_SINGLE_VIS")
      (fields (field (name "COPYRIGHT") "Copyright (C) 2026 Ultra Librarian. All rights reserved."))
      (libsource (lib "eagle-import") (part "SIR882DP-T1-GE3"))
    )
    (comp (ref "Q3B")
      (value "SIS468DN-T1-GE3")
      (footprint "eagle-import:VISHAY_SIS468DN-T1-GE3")
      (fields (field (name "MF") "Vishay Siliconix"))
      (libsource (lib "eagle-import") (part "SIS468DN-T1-GE3"))
    )
    (comp (ref "Q4")
      (value "MMBT3906LT1G")
      (footprint "eagle-import:SOT95P240X111-3N")
      (fields (field (name "MANUFACTURER") "Onsemi") (field (name "CREATOR") "ASHISH"))
      (libsource (lib "eagle-import") (part "MMBT3906LT1G"))
    )
    (comp (ref "Q4A")
      (value "SIR882DP-T1-GE3")
      (footprint "eagle-import:POWERPAK_SO-8_SINGLE_VIS")
      (fields (field (name "COPYRIGHT") "Copyright (C) 2026 Ultra Librarian. All rights reserved."))
      (libsource (lib "eagle-import") (part "SIR882DP-T1-GE3"))
    )
    (comp (ref "Q4B")
      (value "SIS468DN-T1-GE3")
      (footprint "eagle-import:VISHAY_SIS468DN-T1-GE3")
      (fields (field (name "MF") "Vishay Siliconix"))
      (libsource (lib "eagle-import") (part "SIS468DN-T1-GE3"))
    )
    (comp (ref "Q5")
      (value "FDN5618P")
      (footprint "eagle-import:SSOT-3")
      (libsource (lib "eagle-import") (part "FDN5618P"))
    )
    (comp (ref "Q5A")
      (value "SIR882DP-T1-GE3")
      (footprint "eagle-import:POWERPAK_SO-8_SINGLE_VIS")
      (fields (field (name "COPYRIGHT") "Copyright (C) 2026 Ultra Librarian. All rights reserved."))
      (libsource (lib "eagle-import") (part "SIR882DP-T1-GE3"))
    )
    (comp (ref "Q5B")
      (value "SIS468DN-T1-GE3")
      (footprint "eagle-import:VISHAY_SIS468DN-T1-GE3")
      (fields (field (name "MF") "Vishay Siliconix"))
      (libsource (lib "eagle-import") (part "SIS468DN-T1-GE3"))
    )
    (comp (ref "Q6")
      (value "CMPT3904E_TR_PBFREE")
      (footprint "eagle-import:CMPT-3904-NPN_CNS")
      (fields
        (field (name "MANUFACTURER_PART_NUMBER") "CMPT3904E TR PBFREE")
        (field (name "COPYRIGHT") "Copyright (C) 2026 Ultra Librarian. All rights reserved.")
      )
      (libsource (lib "eagle-import") (part "CMPT3904E_TR_PBFREE"))
    )
    (comp (ref "Q6A")
      (value "SIR882DP-T1-GE3")
      (footprint "eagle-import:POWERPAK_SO-8_SINGLE_VIS")
      (fields (field (name "COPYRIGHT") "Copyright (C) 2026 Ultra Librarian. All rights reserved."))
      (libsource (lib "eagle-import") (part "SIR882DP-T1-GE3"))
    )
    (comp (ref "Q6B")
      (value "SIS468DN-T1-GE3")
      (footprint "eagle-import:VISHAY_SIS468DN-T1-GE3")
      (fields (field (name "MF") "Vishay Siliconix"))
      (libsource (lib "eagle-import") (part "SIS468DN-T1-GE3"))
    )
    (comp (ref "Q9A")
      (value "SIR882DP-T1-GE3")
      (footprint "eagle-import:POWERPAK_SO-8_SINGLE_VIS")
      (fields (field (name "COPYRIGHT") "Copyright (C) 2026 Ultra Librarian. All rights reserved."))
      (libsource (lib "eagle-import") (part "SIR882DP-T1-GE3"))
    )
    (comp (ref "Q9B")
      (value "SIS468DN-T1-GE3")
      (footprint "eagle-import:VISHAY_SIS468DN-T1-GE3")
      (fields (field (name "MF") "Vishay Siliconix"))
      (libsource (lib "eagle-import") (part "SIS468DN-T1-GE3"))
    )
    (comp (ref "Q10A")
      (value "SIR882DP-T1-GE3")
      (footprint "eagle-import:POWERPAK_SO-8_SINGLE_VIS")
      (fields (field (name "COPYRIGHT") "Copyright (C) 2026 Ultra Librarian. All rights reserved."))
      (libsource (lib "eagle-import") (part "SIR882DP-T1-GE3"))
    )
    (comp (ref "Q10B")
      (value "SIS468DN-T1-GE3")
      (footprint "eagle-import:VISHAY_SIS468DN-T1-GE3")
      (fields (field (name "MF") "Vishay Siliconix"))
      (libsource (lib "eagle-import") (part "SIS468DN-T1-GE3"))
    )
    (comp (ref "Q11A")
      (value "SIR882DP-T1-GE3")
      (footprint "eagle-import:POWERPAK_SO-8_SINGLE_VIS")
      (fields (field (name "COPYRIGHT") "Copyright (C) 2026 Ultra Librarian. All rights reserved."))
      (libsource (lib "eagle-import") (part "SIR882DP-T1-GE3"))
    )
    (comp (ref "Q11B")
      (value "SIS468DN-T1-GE3")
      (footprint "eagle-import:VISHAY_SIS468DN-T1-GE3")
      (fields (field (name "MF") "Vishay Siliconix"))
      (libsource (lib "eagle-import") (part "SIS468DN-T1-GE3"))
    )
    (comp (ref "Q12A")
      (value "SIR882DP-T1-GE3")
      (footprint "eagle-import:POWERPAK_SO-8_SINGLE_VIS")
      (fields (field (name "COPYRIGHT") "Copyright (C) 2026 Ultra Librarian. All rights reserved."))
      (libsource (lib "eagle-import") (part "SIR882DP-T1-GE3"))
    )
    (comp (ref "Q12B")
      (value "SIS468DN-T1-GE3")
      (footprint "eagle-import:VISHAY_SIS468DN-T1-GE3")
      (fields (field (name "MF") "Vishay Siliconix"))
      (libsource (lib "eagle-import") (part "SIS468DN-T1-GE3"))
    )
    (comp (ref "R1")
      (value "1M")
      (footprint "eagle-import:0805")
      (libsource (lib "eagle-import") (part "RES"))
    )
    (comp (ref "R3A")
      (value "20")
      (footprint "eagle-import:R1206")
      (libsource (lib "eagle-import") (part "R-US_R1206"))
    )
    (comp (ref "R3B")
      (value "20")
      (footprint "eagle-import:R1206")
      (libsource (lib "eagle-import") (part "R-US_R1206"))
    )
    (comp (ref "R3C")
      (value "5.1")
      (footprint "eagle-import:0805")
      (libsource (lib "eagle-import") (part "RES"))
    )
    (comp (ref "R3F")
      (value "5.1")
      (footprint "eagle-import:0805")
      (libsource (lib "eagle-import") (part "RES"))
    )
    (comp (ref "R3G")
      (value "20")
      (footprint "eagle-import:0805")
      (libsource (lib "eagle-import") (part "RES"))
    )
    (comp (ref "R3H")
      (value "20")
      (footprint "eagle-import:0805")
      (libsource (lib "eagle-import") (part "RES"))
    )
    (comp (ref "R3J")
      (value "2k")
      (footprint "eagle-import:R0805")
      (libsource (lib "eagle-import") (part "R-US_R0805"))
    )
    (comp (ref "R4")
      (value "1.27M")
      (footprint "eagle-import:0805")
      (libsource (lib "eagle-import") (part "RES"))
    )
    (comp (ref "R4A")
      (value "20")
      (footprint "eagle-import:R1206")
      (libsource (lib "eagle-import") (part "R-US_R1206"))
    )
    (comp (ref "R4B")
      (value "20")
      (footprint "eagle-import:R1206")
      (libsource (lib "eagle-import") (part "R-US_R1206"))
    )
    (comp (ref "R4C")
      (value "5.1")
      (footprint "eagle-import:0805")
      (libsource (lib "eagle-import") (part "RES"))
    )
    (comp (ref "R4F")
      (value "5.1")
      (footprint "eagle-import:0805")
      (libsource (lib "eagle-import") (part "RES"))
    )
    (comp (ref "R4G")
      (value "20")
      (footprint "eagle-import:0805")
      (libsource (lib "eagle-import") (part "RES"))
    )
    (comp (ref "R4H")
      (value "20")
      (footprint "eagle-import:0805")
      (libsource (lib "eagle-import") (part "RES"))
    )
    (comp (ref "R4J")
      (value "2k")
      (footprint "eagle-import:R0805")
      (libsource (lib "eagle-import") (part "R-US_R0805"))
    )
    (comp (ref "R5A")
      (value "20")
      (footprint "eagle-import:R1206")
      (libsource (lib "eagle-import") (part "R-US_R1206"))
    )
    (comp (ref "R5B")
      (value "20")
      (footprint "eagle-import:R1206")
      (libsource (lib "eagle-import") (part "R-US_R1206"))
    )
    (comp (ref "R5C")
      (value "5.1")
      (footprint "eagle-import:0805")
      (libsource (lib "eagle-import") (part "RES"))
    )
    (comp (ref "R5F")
      (value "5.1")
      (footprint "eagle-import:0805")
      (libsource (lib "eagle-import") (part "RES"))
    )
    (comp (ref "R5G")
      (value "20")
      (footprint "eagle-import:0805")
      (libsource (lib "eagle-import") (part "RES"))
    )
    (comp (ref "R5H")
      (value "20")
      (footprint "eagle-import:0805")
      (libsource (lib "eagle-import") (part "RES"))
    )
    (comp (ref "R5J")
      (value "2k")
      (footprint "eagle-import:R0805")
      (libsource (lib "eagle-import") (part "R-US_R0805"))
    )
    (comp (ref "R6")
      (value "6.81")
      (footprint "eagle-import:0805")
      (libsource (lib "eagle-import") (part "RES"))
    )
    (comp (ref "R6A")
      (value "20")
      (footprint "eagle-import:R1206")
      (libsource (lib "eagle-import") (part "R-US_R1206"))
    )
    (comp (ref "R6B")
      (value "20")
      (footprint "eagle-import:R1206")
      (libsource (lib "eagle-import") (part "R-US_R1206"))
    )
    (comp (ref "R6C")
      (value "5.1")
      (footprint "eagle-import:0805")
      (libsource (lib "eagle-import") (part "RES"))
    )
    (comp (ref "R6F")
      (value "5.1")
      (footprint "eagle-import:0805")
      (libsource (lib "eagle-import") (part "RES"))
    )
    (comp (ref "R6G")
      (value "20")
      (footprint "eagle-import:0805")
      (libsource (lib "eagle-import") (part "RES"))
    )
    (comp (ref "R6H")
      (value "20")
      (footprint "eagle-import:0805")
      (libsource (lib "eagle-import") (part "RES"))
    )
    (comp (ref "R6J")
      (value "2k")
      (footprint "eagle-import:R0805")
      (libsource (lib "eagle-import") (part "R-US_R0805"))
    )
    (comp (ref "R7")
      (value "1M")
      (footprint "eagle-import:0805")
      (libsource (lib "eagle-import") (part "RES"))
    )
    (comp (ref "R8")
      (value "1.27M")
      (footprint "eagle-import:0805")
      (libsource (lib "eagle-import") (part "RES"))
    )
    (comp (ref "R9A")
      (value "20")
      (footprint "eagle-import:R1206")
      (libsource (lib "eagle-import") (part "R-US_R1206"))
    )
    (comp (ref "R9B")
      (value "20")
      (footprint "eagle-import:R1206")
      (libsource (lib "eagle-import") (part "R-US_R1206"))
    )
    (comp (ref "R9C")
      (value "5.1")
      (footprint "eagle-import:0805")
      (libsource (lib "eagle-import") (part "RES"))
    )
    (comp (ref "R9F")
      (value "5.1")
      (footprint "eagle-import:0805")
      (libsource (lib "eagle-import") (part "RES"))
    )
    (comp (ref "R9G")
      (value "20")
      (footprint "eagle-import:0805")
      (libsource (lib "eagle-import") (part "RES"))
    )
    (comp (ref "R9H")
      (value "20")
      (footprint "eagle-import:0805")
      (libsource (lib "eagle-import") (part "RES"))
    )
    (comp (ref "R9J")
      (value "2k")
      (footprint "eagle-import:R0805")
      (libsource (lib "eagle-import") (part "R-US_R0805"))
    )
    (comp (ref "R10")
      (value "6.81")
      (footprint "eagle-import:0805")
      (libsource (lib "eagle-import") (part "RES"))
    )
    (comp (ref "R10A")
      (value "20")
      (footprint "eagle-import:R1206")
      (libsource (lib "eagle-import") (part "R-US_R1206"))
    )
    (comp (ref "R10B")
      (value "20")
      (footprint "eagle-import:R1206")
      (libsource (lib "eagle-import") (part "R-US_R1206"))
    )
    (comp (ref "R10C")
      (value "5.1")
      (footprint "eagle-import:0805")
      (libsource (lib "eagle-import") (part "RES"))
    )
    (comp (ref "R10F")
      (value "5.1")
      (footprint "eagle-import:0805")
      (libsource (lib "eagle-import") (part "RES"))
    )
    (comp (ref "R10G")
      (value "20")
      (footprint "eagle-import:0805")
      (libsource (lib "eagle-import") (part "RES"))
    )
    (comp (ref "R10H")
      (value "20")
      (footprint "eagle-import:0805")
      (libsource (lib "eagle-import") (part "RES"))
    )
    (comp (ref "R10J")
      (value "2k")
      (footprint "eagle-import:R0805")
      (libsource (lib "eagle-import") (part "R-US_R0805"))
    )
    (comp (ref "R11")
      (value "0")
      (footprint "eagle-import:R2512")
      (libsource (lib "eagle-import") (part "R-US_R2512"))
    )
    (comp (ref "R11A")
      (value "20")
      (footprint "eagle-import:R1206")
      (libsource (lib "eagle-import") (part "R-US_R1206"))
    )
    (comp (ref "R11B")
      (value "20")
      (footprint "eagle-import:R1206")
      (libsource (lib "eagle-import") (part "R-US_R1206"))
    )
    (comp (ref "R11C")
      (value "5.1")
      (footprint "eagle-import:0805")
      (libsource (lib "eagle-import") (part "RES"))
    )
    (comp (ref "R11F")
      (value "5.1")
      (footprint "eagle-import:0805")
      (libsource (lib "eagle-import") (part "RES"))
    )
    (comp (ref "R11G")
      (value "20")
      (footprint "eagle-import:0805")
      (libsource (lib "eagle-import") (part "RES"))
    )
    (comp (ref "R11H")
      (value "20")
      (footprint "eagle-import:0805")
      (libsource (lib "eagle-import") (part "RES"))
    )
    (comp (ref "R11J")
      (value "2k")
      (footprint "eagle-import:R0805")
      (libsource (lib "eagle-import") (part "R-US_R0805"))
    )
    (comp (ref "R12")
      (value "0")
      (footprint "eagle-import:R2512")
      (libsource (lib "eagle-import") (part "R-US_R2512"))
    )
    (comp (ref "R12A")
      (value "20")
      (footprint "eagle-import:R1206")
      (libsource (lib "eagle-import") (part "R-US_R1206"))
    )
    (comp (ref "R12B")
      (value "20")
      (footprint "eagle-import:R1206")
      (libsource (lib "eagle-import") (part "R-US_R1206"))
    )
    (comp (ref "R12C")
      (value "5.1")
      (footprint "eagle-import:0805")
      (libsource (lib "eagle-import") (part "RES"))
    )
    (comp (ref "R12F")
      (value "5.1")
      (footprint "eagle-import:0805")
      (libsource (lib "eagle-import") (part "RES"))
    )
    (comp (ref "R12G")
      (value "20")
      (footprint "eagle-import:0805")
      (libsource (lib "eagle-import") (part "RES"))
    )
    (comp (ref "R12H")
      (value "20")
      (footprint "eagle-import:0805")
      (libsource (lib "eagle-import") (part "RES"))
    )
    (comp (ref "R12J")
      (value "2k")
      (footprint "eagle-import:R0805")
      (libsource (lib "eagle-import") (part "R-US_R0805"))
    )
    (comp (ref "R15")
      (value "0")
      (footprint "eagle-import:R2512")
      (libsource (lib "eagle-import") (part "R-US_R2512"))
    )
    (comp (ref "R16")
      (value "0")
      (footprint "eagle-import:R2512")
      (libsource (lib "eagle-import") (part "R-US_R2512"))
    )
    (comp (ref "R19")
      (value "23.7k")
      (footprint "eagle-import:0805")
      (libsource (lib "eagle-import") (part "RES"))
    )
    (comp (ref "R20")
      (value "33.2k")
      (footprint "eagle-import:0805")
      (libsource (lib "eagle-import") (part "RES"))
    )
    (comp (ref "R21")
      (value "23.7k")
      (footprint "eagle-import:0805")
      (libsource (lib "eagle-import") (part "RES"))
    )
    (comp (ref "R22")
      (value "33.2k")
      (footprint "eagle-import:0805")
      (libsource (lib "eagle-import") (part "RES"))
    )
    (comp (ref "R24")
      (value "23.7k")
      (footprint "eagle-import:0805")
      (libsource (lib "eagle-import") (part "RES"))
    )
    (comp (ref "R53")
      (value "100k")
      (footprint "eagle-import:0805")
      (libsource (lib "eagle-import") (part "RES"))
    )
    (comp (ref "R54")
      (value "20")
      (footprint "eagle-import:0805")
      (libsource (lib "eagle-import") (part "RES"))
    )
    (comp (ref "R55")
      (value "20")
      (footprint "eagle-import:0805")
      (libsource (lib "eagle-import") (part "RES"))
    )
    (comp (ref "R56")
      (value "2k")
      (footprint "eagle-import:0805")
      (libsource (lib "eagle-import") (part "RES"))
    )
    (comp (ref "R58")
      (value "2k")
      (footprint "eagle-import:0805")
      (libsource (lib "eagle-import") (part "RES"))
    )
    (comp (ref "RS3A")
      (value "0.005")
      (footprint "eagle-import:RESC1632X60N")
      (libsource (lib "eagle-import") (part "PRL1632-R010-F-T1"))
    )
    (comp (ref "RS3B")
      (value "0.01")
      (footprint "eagle-import:RESC1632X60N")
      (libsource (lib "eagle-import") (part "PRL1632-R010-F-T1"))
    )
    (comp (ref "RS4A")
      (value "0.005")
      (footprint "eagle-import:RESC1632X60N")
      (libsource (lib "eagle-import") (part "PRL1632-R010-F-T1"))
    )
    (comp (ref "RS4B")
      (value "0.01")
      (footprint "eagle-import:RESC1632X60N")
      (libsource (lib "eagle-import") (part "PRL1632-R010-F-T1"))
    )
    (comp (ref "RS5A")
      (value "0.005")
      (footprint "eagle-import:RESC1632X60N")
      (libsource (lib "eagle-import") (part "PRL1632-R010-F-T1"))
    )
    (comp (ref "RS5B")
      (value "0.01")
      (footprint "eagle-import:RESC1632X60N")
      (libsource (lib "eagle-import") (part "PRL1632-R010-F-T1"))
    )
    (comp (ref "RS6A")
      (value "0.005")
      (footprint "eagle-import:RESC1632X60N")
      (libsource (lib "eagle-import") (part "PRL1632-R010-F-T1"))
    )
    (comp (ref "RS6B")
      (value "0.01")
      (footprint "eagle-import:RESC1632X60N")
      (libsource (lib "eagle-import") (part "PRL1632-R010-F-T1"))
    )
    (comp (ref "RS9A")
      (value "0.005")
      (footprint "eagle-import:RESC1632X60N")
      (libsource (lib "eagle-import") (part "PRL1632-R010-F-T1"))
    )
    (comp (ref "RS9B")
      (value "0.01")
      (footprint "eagle-import:RESC1632X60N")
      (libsource (lib "eagle-import") (part "PRL1632-R010-F-T1"))
    )
    (comp (ref "RS10A")
      (value "0.005")
      (footprint "eagle-import:RESC1632X60N")
      (libsource (lib "eagle-import") (part "PRL1632-R010-F-T1"))
    )
    (comp (ref "RS10B")
      (value "0.01")
      (footprint "eagle-import:RESC1632X60N")
      (libsource (lib "eagle-import") (part "PRL1632-R010-F-T1"))
    )
    (comp (ref "RS11A")
      (value "0.005")
      (footprint "eagle-import:RESC1632X60N")
      (libsource (lib "eagle-import") (part "PRL1632-R010-F-T1"))
    )
    (comp (ref "RS11B")
      (value "0.01")
      (footprint "eagle-import:RESC1632X60N")
      (libsource (lib "eagle-import") (part "PRL1632-R010-F-T1"))
    )
    (comp (ref "RS12A")
      (value "0.005")
      (footprint "eagle-import:RESC1632X60N")
      (libsource (lib "eagle-import") (part "PRL1632-R010-F-T1"))
    )
    (comp (ref "RS12B")
      (value "0.01")
      (footprint "eagle-import:RESC1632X60N")
      (libsource (lib "eagle-import") (part "PRL1632-R010-F-T1"))
    )
    (comp (ref "T3")
      (value "750312504")
      (footprint "eagle-import:WE-FLYLT_EP13_2381")
      (libsource (lib "eagle-import") (part "750312504"))
    )
    (comp (ref "T4")
      (value "750312504")
      (footprint "eagle-import:WE-FLYLT_EP13_2381")
      (libsource (lib "eagle-import") (part "750312504"))
    )
    (comp (ref "T5")
      (value "750312504")
      (footprint "eagle-import:WE-FLYLT_EP13_2381")
      (libsource (lib "eagle-import") (part "750312504"))
    )
    (comp (ref "T6")
      (value "750312504")
      (footprint "eagle-import:WE-FLYLT_EP13_2381")
      (libsource (lib "eagle-import") (part "750312504"))
    )
    (comp (ref "T9")
      (value "750312504")
      (footprint "eagle-import:WE-FLYLT_EP13_2381")
      (libsource (lib "eagle-import") (part "750312504"))
    )
    (comp (ref "T10")
      (value "750312504")
      (footprint "eagle-import:WE-FLYLT_EP13_2381")
      (libsource (lib "eagle-import") (part "750312504"))
    )
    (comp (ref "T11")
      (value "750312504")
      (footprint "eagle-import:WE-FLYLT_EP13_2381")
      (libsource (lib "eagle-import") (part "750312504"))
    )
    (comp (ref "T12")
      (value "750312504")
      (footprint "eagle-import:WE-FLYLT_EP13_2381")
      (libsource (lib "eagle-import") (part "750312504"))
    )
    (comp (ref "U1")
      (value "LTC3300ILXE-1PBF")
      (footprint "eagle-import:05-08-1832_ADI")
      (fields
        (field (name "MANUFACTURER_PART_NUMBER") "LTC3300ILXE-1#PBF")
        (field (name "COPYRIGHT") "Copyright (C) 2026 Ultra Librarian. All rights reserved.")
      )
      (libsource (lib "eagle-import") (part "LTC3300ILXE-1PBF"))
    )
    (comp (ref "U2")
      (value "LTC3300ILXE-1PBF")
      (footprint "eagle-import:05-08-1832_ADI")
      (fields
        (field (name "MANUFACTURER_PART_NUMBER") "LTC3300ILXE-1#PBF")
        (field (name "COPYRIGHT") "Copyright (C) 2026 Ultra Librarian. All rights reserved.")
      )
      (libsource (lib "eagle-import") (part "LTC3300ILXE-1PBF"))
    )
    (comp (ref "VOLT_TAPS")
      (value "B9P-VH")
      (footprint "eagle-import:B9P-VH")
      (libsource (lib "eagle-import") (part "B9P-VH"))
    )
    (comp (ref "WDTA")
      (value "2501-2-00-80-00-00-07-0")
      (footprint "eagle-import:MILMAX_2501-2-00-80-00-00-07-0")
      (fields (field (name "MANUFACTURER") "MILMAX"))
      (libsource (lib "eagle-import") (part "2501-2-00-80-00-00-07-0"))
    )
    (comp (ref "WDTC")
      (value "2501-2-00-80-00-00-07-0")
      (footprint "eagle-import:MILMAX_2501-2-00-80-00-00-07-0")
      (fields (field (name "MANUFACTURER") "MILMAX"))
      (libsource (lib "eagle-import") (part "2501-2-00-80-00-00-07-0"))
    )
  )
  (nets
    (net (code "1") (name "/BAT+") (class "Default")
      (node (ref "BATT") (pin "1") (pinfunction "1_1") (pintype "passive"))
      (node (ref "F12") (pin "2") (pinfunction "2_2") (pintype "bidirectional"))
      (node (ref "F13") (pin "1") (pinfunction "1_1") (pintype "bidirectional"))
      (node (ref "F14") (pin "1") (pinfunction "1_1") (pintype "bidirectional"))
    )
    (net (code "2") (name "/BOOST+") (class "Default")
      (node (ref "C4") (pin "1") (pinfunction "1_1") (pintype "passive"))
      (node (ref "D1") (pin "1") (pinfunction "C_1") (pintype "passive"))
      (node (ref "U1") (pin "40") (pinfunction "BOOST+_40") (pintype "power_in"))
    )
    (net (code "3") (name "/BOOST-") (class "Default")
      (node (ref "C3") (pin "2") (pinfunction "2_2") (pintype "passive"))
      (node (ref "U1") (pin "41") (pinfunction "BOOST-_41") (pintype "power_in"))
    )
    (net (code "4") (name "/BOT6_TS") (class "Default")
      (node (ref "C3F") (pin "2") (pinfunction "2_2") (pintype "passive"))
      (node (ref "C3R") (pin "1") (pinfunction "1_1") (pintype "passive"))
      (node (ref "C4F") (pin "2") (pinfunction "2_2") (pintype "passive"))
      (node (ref "C4R") (pin "1") (pinfunction "1_1") (pintype "passive"))
      (node (ref "C5F") (pin "2") (pinfunction "2_2") (pintype "passive"))
      (node (ref "C5R") (pin "1") (pinfunction "1_1") (pintype "passive"))
      (node (ref "C6F") (pin "2") (pinfunction "2_2") (pintype "passive"))
      (node (ref "C6R") (pin "1") (pinfunction "1_1") (pintype "passive"))
      (node (ref "E8") (pin "1") (pinfunction "1_1") (pintype "passive"))
      (node (ref "F13") (pin "2") (pinfunction "2_2") (pintype "bidirectional"))
      (node (ref "R4") (pin "2") (pinfunction "2_2") (pintype "passive"))
      (node (ref "T3") (pin "7") (pinfunction "7_7") (pintype "passive"))
      (node (ref "T4") (pin "7") (pinfunction "7_7") (pintype "passive"))
      (node (ref "T5") (pin "7") (pinfunction "7_7") (pintype "passive"))
      (node (ref "T6") (pin "7") (pinfunction "7_7") (pintype "passive"))
    )
    (net (code "5") (name "/C3") (class "Default")
      (node (ref "C10") (pin "2") (pinfunction "2_2") (pintype "passive"))
      (node (ref "C12") (pin "1") (pinfunction "1_1") (pintype "passive"))
      (node (ref "C3A") (pin "1") (pinfunction "1_1") (pintype "passive"))
      (node (ref "C3B") (pin "1") (pinfunction "1_1") (pintype "passive"))
      (node (ref "C3E") (pin "1") (pinfunction "1_1") (pintype "passive"))
      (node (ref "C3K") (pin "1") (pinfunction "1_1") (pintype "passive"))
      (node (ref "C4A") (pin "2") (pinfunction "2_2") (pintype "passive"))
      (node (ref "C4B") (pin "2") (pinfunction "2_2") (pintype "passive"))
      (node (ref "C4G") (pin "2") (pinfunction "2_2") (pintype "passive"))
      (node (ref "C4K") (pin "2") (pinfunction "2_2") (pintype "passive"))
      (node (ref "D3E") (pin "P$1") (pinfunction "P$3_P$1") (pintype "bidirectional"))
      (node (ref "D4C") (pin "A") (pinfunction "A_A") (pintype "passive"))
      (node (ref "D4E") (pin "P$2") (pinfunction "P$1_P$2") (pintype "bidirectional"))
      (node (ref "D4E") (pin "P$3") (pinfunction "P$2_P$3") (pintype "bidirectional"))
      (node (ref "E4") (pin "1") (pinfunction "1_1") (pintype "passive"))
      (node (ref "F3") (pin "2") (pinfunction "2_2") (pintype "bidirectional"))
      (node (ref "R4J") (pin "1") (pinfunction "1_1") (pintype "passive"))
      (node (ref "RS4A") (pin "1") (pinfunction "1_1") (pintype "passive"))
      (node (ref "T3") (pin "1") (pinfunction "1_1") (pintype "passive"))
      (node (ref "T3") (pin "2") (pinfunction "2_2") (pintype "passive"))
      (node (ref "U1") (pin "30") (pinfunction "C3_30") (pintype "power_in"))
      (node (ref "VOLT_TAPS") (pin "2") (pinfunction "2_2") (pintype "passive"))
    )
    (net (code "6") (name "/C4") (class "Default")
      (node (ref "C4A") (pin "1") (pinfunction "1_1") (pintype "passive"))
      (node (ref "C4B") (pin "1") (pinfunction "1_1") (pintype "passive"))
      (node (ref "C4E") (pin "1") (pinfunction "1_1") (pintype "passive"))
      (node (ref "C4K") (pin "1") (pinfunction "1_1") (pintype "passive"))
      (node (ref "C5A") (pin "2") (pinfunction "2_2") (pintype "passive"))
      (node (ref "C5B") (pin "2") (pinfunction "2_2") (pintype "passive"))
      (node (ref "C5G") (pin "2") (pinfunction "2_2") (pintype "passive"))
      (node (ref "C5K") (pin "2") (pinfunction "2_2") (pintype "passive"))
      (node (ref "C9") (pin "2") (pinfunction "2_2") (pintype "passive"))
      (node (ref "D4E") (pin "P$1") (pinfunction "P$3_P$1") (pintype "bidirectional"))
      (node (ref "D5C") (pin "A") (pinfunction "A_A") (pintype "passive"))
      (node (ref "D5E") (pin "P$2") (pinfunction "P$1_P$2") (pintype "bidirectional"))
      (node (ref "D5E") (pin "P$3") (pinfunction "P$2_P$3") (pintype "bidirectional"))
      (node (ref "E5") (pin "1") (pinfunction "1_1") (pintype "passive"))
      (node (ref "F4") (pin "1") (pinfunction "1_1") (pintype "bidirectional"))
      (node (ref "R12") (pin "2") (pinfunction "2_2") (pintype "passive"))
      (node (ref "R5J") (pin "1") (pinfunction "1_1") (pintype "passive"))
      (node (ref "RS5A") (pin "1") (pinfunction "1_1") (pintype "passive"))
      (node (ref "T4") (pin "1") (pinfunction "1_1") (pintype "passive"))
      (node (ref "T4") (pin "2") (pinfunction "2_2") (pintype "passive"))
      (node (ref "U1") (pin "33") (pinfunction "C4_33") (pintype "power_in"))
      (node (ref "VOLT_TAPS") (pin "3") (pinfunction "3_3") (pintype "passive"))
    )
    (net (code "7") (name "/C5") (class "Default")
      (node (ref "C10") (pin "1") (pinfunction "1_1") (pintype "passive"))
      (node (ref "C13") (pin "2") (pinfunction "2_2") (pintype "passive"))
      (node (ref "C4") (pin "2") (pinfunction "2_2") (pintype "passive"))
      (node (ref "C5A") (pin "1") (pinfunction "1_1") (pintype "passive"))
      (node (ref "C5B") (pin "1") (pinfunction "1_1") (pintype "passive"))
      (node (ref "C5E") (pin "1") (pinfunction "1_1") (pintype "passive"))
      (node (ref "C5K") (pin "1") (pinfunction "1_1") (pintype "passive"))
      (node (ref "C6A") (pin "2") (pinfunction "2_2") (pintype "passive"))
      (node (ref "C6B") (pin "2") (pinfunction "2_2") (pintype "passive"))
      (node (ref "C6G") (pin "2") (pinfunction "2_2") (pintype "passive"))
      (node (ref "C6K") (pin "2") (pinfunction "2_2") (pintype "passive"))
      (node (ref "D11") (pin "A") (pinfunction "A_A") (pintype "passive"))
      (node (ref "D5E") (pin "P$1") (pinfunction "P$3_P$1") (pintype "bidirectional"))
      (node (ref "D6C") (pin "A") (pinfunction "A_A") (pintype "passive"))
      (node (ref "D6E") (pin "P$2") (pinfunction "P$1_P$2") (pintype "bidirectional"))
      (node (ref "D6E") (pin "P$3") (pinfunction "P$2_P$3") (pintype "bidirectional"))
      (node (ref "E6") (pin "1") (pinfunction "1_1") (pintype "passive"))
      (node (ref "F5") (pin "2") (pinfunction "2_2") (pintype "bidirectional"))
      (node (ref "R58") (pin "1") (pinfunction "1_1") (pintype "passive"))
      (node (ref "R6J") (pin "1") (pinfunction "1_1") (pintype "passive"))
      (node (ref "RS6A") (pin "1") (pinfunction "1_1") (pintype "passive"))
      (node (ref "T5") (pin "1") (pinfunction "1_1") (pintype "passive"))
      (node (ref "T5") (pin "2") (pinfunction "2_2") (pintype "passive"))
      (node (ref "U1") (pin "36") (pinfunction "C5_36") (pintype "power_in"))
      (node (ref "VOLT_TAPS") (pin "4") (pinfunction "4_4") (pintype "passive"))
    )
    (net (code "8") (name "/C6") (class "Default")
      (node (ref "C10H") (pin "1") (pinfunction "1_1") (pintype "passive"))
      (node (ref "C10R") (pin "2") (pinfunction "2_2") (pintype "passive"))
      (node (ref "C11H") (pin "1") (pinfunction "1_1") (pintype "passive"))
      (node (ref "C11R") (pin "2") (pinfunction "2_2") (pintype "passive"))
      (node (ref "C12H") (pin "1") (pinfunction "1_1") (pintype "passive"))
      (node (ref "C12R") (pin "2") (pinfunction "2_2") (pintype "passive"))
      (node (ref "C13") (pin "1") (pinfunction "1_1") (pintype "passive"))
      (node (ref "C17") (pin "2") (pinfunction "2_2") (pintype "passive"))
      (node (ref "C18") (pin "2") (pinfunction "2_2") (pintype "passive"))
      (node (ref "C5") (pin "1") (pinfunction "1_1") (pintype "passive"))
      (node (ref "C6") (pin "1") (pinfunction "1_1") (pintype "passive"))
      (node (ref "C6A") (pin "1") (pinfunction "1_1") (pintype "passive"))
      (node (ref "C6B") (pin "1") (pinfunction "1_1") (pintype "passive"))
      (node (ref "C6E") (pin "1") (pinfunction "1_1") (pintype "passive"))
      (node (ref "C6K") (pin "1") (pinfunction "1_1") (pintype "passive"))
      (node (ref "C9A") (pin "2") (pinfunction "2_2") (pintype "passive"))
      (node (ref "C9B") (pin "2") (pinfunction "2_2") (pintype "passive"))
      (node (ref "C9G") (pin "2") (pinfunction "2_2") (pintype "passive"))
      (node (ref "C9H") (pin "1") (pinfunction "1_1") (pintype "passive"))
      (node (ref "C9K") (pin "2") (pinfunction "2_2") (pintype "passive"))
      (node (ref "C9R") (pin "2") (pinfunction "2_2") (pintype "passive"))
      (node (ref "D6E") (pin "P$1") (pinfunction "P$3_P$1") (pintype "bidirectional"))
      (node (ref "D9") (pin "A") (pinfunction "A_A") (pintype "passive"))
      (node (ref "D9C") (pin "A") (pinfunction "A_A") (pintype "passive"))
      (node (ref "D9E") (pin "P$2") (pinfunction "P$1_P$2") (pintype "bidirectional"))
      (node (ref "D9E") (pin "P$3") (pinfunction "P$2_P$3") (pintype "bidirectional"))
      (node (ref "E7") (pin "1") (pinfunction "1_1") (pintype "passive"))
      (node (ref "F6") (pin "1") (pinfunction "1_1") (pintype "bidirectional"))
      (node (ref "Q4") (pin "1") (pinfunction "B_1") (pintype "passive"))
      (node (ref "Q6") (pin "1") (pinfunction "1_1") (pintype "passive"))
      (node (ref "R11") (pin "2") (pinfunction "2_2") (pintype "passive"))
      (node (ref "R22") (pin "2") (pinfunction "2_2") (pintype "passive"))
      (node (ref "R24") (pin "2") (pinfunction "2_2") (pintype "passive"))
      (node (ref "R54") (pin "1") (pinfunction "1_1") (pintype "passive"))
      (node (ref "R55") (pin "2") (pinfunction "2_2") (pintype "passive"))
      (node (ref "R56") (pin "1") (pinfunction "1_1") (pintype "passive"))
      (node (ref "R6") (pin "1") (pinfunction "1_1") (pintype "passive"))
      (node (ref "R9J") (pin "1") (pinfunction "1_1") (pintype "passive"))
      (node (ref "RS10B") (pin "1") (pinfunction "1_1") (pintype "passive"))
      (node (ref "RS11B") (pin "1") (pinfunction "1_1") (pintype "passive"))
      (node (ref "RS12B") (pin "1") (pinfunction "1_1") (pintype "passive"))
      (node (ref "RS9A") (pin "1") (pinfunction "1_1") (pintype "passive"))
      (node (ref "RS9B") (pin "1") (pinfunction "1_1") (pintype "passive"))
      (node (ref "T6") (pin "1") (pinfunction "1_1") (pintype "passive"))
      (node (ref "T6") (pin "2") (pinfunction "2_2") (pintype "passive"))
      (node (ref "U1") (pin "39") (pinfunction "C6_39") (pintype "power_in"))
      (node (ref "U2") (pin "15") (pinfunction "CTRL_15") (pintype "input"))
      (node (ref "U2") (pin "21") (pinfunction "V-_2_21") (pintype "power_in"))
      (node (ref "U2") (pin "24") (pinfunction "C1_24") (pintype "power_in"))
      (node (ref "U2") (pin "27") (pinfunction "C2_27") (pintype "power_in"))
      (node (ref "U2") (pin "46") (pinfunction "VMODE_46") (pintype "input"))
      (node (ref "U2") (pin "49") (pinfunction "V-_49") (pintype "power_in"))
      (node (ref "VOLT_TAPS") (pin "5") (pinfunction "5_5") (pintype "passive"))
    )
    (net (code "9") (name "/C9") (class "Default")
      (node (ref "C10A") (pin "2") (pinfunction "2_2") (pintype "passive"))
      (node (ref "C10B") (pin "2") (pinfunction "2_2") (pintype "passive"))
      (node (ref "C10G") (pin "2") (pinfunction "2_2") (pintype "passive"))
      (node (ref "C10K") (pin "2") (pinfunction "2_2") (pintype "passive"))
      (node (ref "C16") (pin "2") (pinfunction "2_2") (pintype "passive"))
      (node (ref "C18") (pin "1") (pinfunction "1_1") (pintype "passive"))
      (node (ref "C9A") (pin "1") (pinfunction "1_1") (pintype "passive"))
      (node (ref "C9B") (pin "1") (pinfunction "1_1") (pintype "passive"))
      (node (ref "C9E") (pin "1") (pinfunction "1_1") (pintype "passive"))
      (node (ref "C9K") (pin "1") (pinfunction "1_1") (pintype "passive"))
      (node (ref "D10C") (pin "A") (pinfunction "A_A") (pintype "passive"))
      (node (ref "D10E") (pin "P$2") (pinfunction "P$1_P$2") (pintype "bidirectional"))
      (node (ref "D10E") (pin "P$3") (pinfunction "P$2_P$3") (pintype "bidirectional"))
      (node (ref "D9E") (pin "P$1") (pinfunction "P$3_P$1") (pintype "bidirectional"))
      (node (ref "E11") (pin "1") (pinfunction "1_1") (pintype "passive"))
      (node (ref "F9") (pin "2") (pinfunction "2_2") (pintype "bidirectional"))
      (node (ref "R10J") (pin "1") (pinfunction "1_1") (pintype "passive"))
      (node (ref "RS10A") (pin "1") (pinfunction "1_1") (pintype "passive"))
      (node (ref "T9") (pin "1") (pinfunction "1_1") (pintype "passive"))
      (node (ref "T9") (pin "2") (pinfunction "2_2") (pintype "passive"))
      (node (ref "U2") (pin "30") (pinfunction "C3_30") (pintype "power_in"))
      (node (ref "VOLT_TAPS") (pin "6") (pinfunction "6_6") (pintype "passive"))
    )
    (net (code "10") (name "/C10") (class "Default")
      (node (ref "C10A") (pin "1") (pinfunction "1_1") (pintype "passive"))
      (node (ref "C10B") (pin "1") (pinfunction "1_1") (pintype "passive"))
      (node (ref "C10E") (pin "1") (pinfunction "1_1") (pintype "passive"))
      (node (ref "C10K") (pin "1") (pinfunction "1_1") (pintype "passive"))
      (node (ref "C11A") (pin "2") (pinfunction "2_2") (pintype "passive"))
      (node (ref "C11B") (pin "2") (pinfunction "2_2") (pintype "passive"))
      (node (ref "C11G") (pin "2") (pinfunction "2_2") (pintype "passive"))
      (node (ref "C11K") (pin "2") (pinfunction "2_2") (pintype "passive"))
      (node (ref "C15") (pin "2") (pinfunction "2_2") (pintype "passive"))
      (node (ref "D10E") (pin "P$1") (pinfunction "P$3_P$1") (pintype "bidirectional"))
      (node (ref "D11C") (pin "A") (pinfunction "A_A") (pintype "passive"))
      (node (ref "D11E") (pin "P$2") (pinfunction "P$1_P$2") (pintype "bidirectional"))
      (node (ref "D11E") (pin "P$3") (pinfunction "P$2_P$3") (pintype "bidirectional"))
      (node (ref "E12") (pin "1") (pinfunction "1_1") (pintype "passive"))
      (node (ref "F10") (pin "1") (pinfunction "1_1") (pintype "bidirectional"))
      (node (ref "R11J") (pin "1") (pinfunction "1_1") (pintype "passive"))
      (node (ref "R16") (pin "2") (pinfunction "2_2") (pintype "passive"))
      (node (ref "RS11A") (pin "1") (pinfunction "1_1") (pintype "passive"))
      (node (ref "T10") (pin "1") (pinfunction "1_1") (pintype "passive"))
      (node (ref "T10") (pin "2") (pinfunction "2_2") (pintype "passive"))
      (node (ref "U2") (pin "33") (pinfunction "C4_33") (pintype "power_in"))
      (node (ref "VOLT_TAPS") (pin "7") (pinfunction "7_7") (pintype "passive"))
    )
    (net (code "11") (name "/C11") (class "Default")
      (node (ref "C11A") (pin "1") (pinfunction "1_1") (pintype "passive"))
      (node (ref "C11B") (pin "1") (pinfunction "1_1") (pintype "passive"))
      (node (ref "C11E") (pin "1") (pinfunction "1_1") (pintype "passive"))
      (node (ref "C11K") (pin "1") (pinfunction "1_1") (pintype "passive"))
      (node (ref "C12A") (pin "2") (pinfunction "2_2") (pintype "passive"))
      (node (ref "C12B") (pin "2") (pinfunction "2_2") (pintype "passive"))
      (node (ref "C12G") (pin "2") (pinfunction "2_2") (pintype "passive"))
      (node (ref "C12K") (pin "2") (pinfunction "2_2") (pintype "passive"))
      (node (ref "C16") (pin "1") (pinfunction "1_1") (pintype "passive"))
      (node (ref "C24") (pin "2") (pinfunction "2_2") (pintype "passive"))
      (node (ref "C8") (pin "2") (pinfunction "2_2") (pintype "passive"))
      (node (ref "D11E") (pin "P$1") (pinfunction "P$3_P$1") (pintype "bidirectional"))
      (node (ref "D12C") (pin "A") (pinfunction "A_A") (pintype "passive"))
      (node (ref "D12E") (pin "P$2") (pinfunction "P$1_P$2") (pintype "bidirectional"))
      (node (ref "D12E") (pin "P$3") (pinfunction "P$2_P$3") (pintype "bidirectional"))
      (node (ref "E13") (pin "1") (pinfunction "1_1") (pintype "passive"))
      (node (ref "F11") (pin "2") (pinfunction "2_2") (pintype "bidirectional"))
      (node (ref "R12J") (pin "1") (pinfunction "1_1") (pintype "passive"))
      (node (ref "RS12A") (pin "1") (pinfunction "1_1") (pintype "passive"))
      (node (ref "T11") (pin "1") (pinfunction "1_1") (pintype "passive"))
      (node (ref "T11") (pin "2") (pinfunction "2_2") (pintype "passive"))
      (node (ref "U2") (pin "36") (pinfunction "C5_36") (pintype "power_in"))
      (node (ref "VOLT_TAPS") (pin "8") (pinfunction "8_8") (pintype "passive"))
    )
    (net (code "12") (name "/C12") (class "Default")
      (node (ref "C12A") (pin "1") (pinfunction "1_1") (pintype "passive"))
      (node (ref "C12B") (pin "1") (pinfunction "1_1") (pintype "passive"))
      (node (ref "C12E") (pin "1") (pinfunction "1_1") (pintype "passive"))
      (node (ref "C12K") (pin "1") (pinfunction "1_1") (pintype "passive"))
      (node (ref "C24") (pin "1") (pinfunction "1_1") (pintype "passive"))
      (node (ref "D12E") (pin "P$1") (pinfunction "P$3_P$1") (pintype "bidirectional"))
      (node (ref "E14") (pin "1") (pinfunction "1_1") (pintype "passive"))
      (node (ref "F12") (pin "1") (pinfunction "1_1") (pintype "bidirectional"))
      (node (ref "R10") (pin "2") (pinfunction "2_2") (pintype "passive"))
      (node (ref "R15") (pin "2") (pinfunction "2_2") (pintype "passive"))
      (node (ref "T12") (pin "1") (pinfunction "1_1") (pintype "passive"))
      (node (ref "T12") (pin "2") (pinfunction "2_2") (pintype "passive"))
      (node (ref "U2") (pin "39") (pinfunction "C6_39") (pintype "power_in"))
      (node (ref "U2") (pin "43") (pinfunction "SDOI_43") (pintype "bidirectional"))
      (node (ref "U2") (pin "44") (pinfunction "SCKO_44") (pintype "output"))
      (node (ref "U2") (pin "45") (pinfunction "CSBO_45") (pintype "output"))
      (node (ref "VOLT_TAPS") (pin "9") (pinfunction "9_9") (pintype "passive"))
    )
    (net (code "13") (name "/CSBI") (class "Default")
      (node (ref "COMM") (pin "3") (pinfunction "3_3") (pintype "passive"))
      (node (ref "U1") (pin "16") (pinfunction "CSBI_16") (pintype "input"))
    )
    (net (code "14") (name "/CSBO") (class "Default")
      (node (ref "D5") (pin "C") (pinfunction "C_C") (pintype "passive"))
      (node (ref "U1") (pin "45") (pinfunction "CSBO_45") (pintype "output"))
    )
    (net (code "15") (name "/G1P") (class "Default")
      (node (ref "U1") (pin "23") (pinfunction "G1P_23") (pintype "output"))
    )
    (net (code "16") (name "/G1S") (class "Default")
      (node (ref "U1") (pin "11") (pinfunction "G1S_11") (pintype "output"))
    )
    (net (code "17") (name "/G2P") (class "Default")
      (node (ref "U1") (pin "26") (pinfunction "G2P_26") (pintype "output"))
    )
    (net (code "18") (name "/G2S") (class "Default")
      (node (ref "U1") (pin "9") (pinfunction "G2S_9") (pintype "output"))
    )
    (net (code "19") (name "/G3P") (class "Default")
      (node (ref "D3C") (pin "K") (pinfunction "C_K") (pintype "passive"))
      (node (ref "D3D") (pin "A") (pinfunction "A_A") (pintype "passive"))
      (node (ref "R3C") (pin "1") (pinfunction "1_1") (pintype "passive"))
      (node (ref "U1") (pin "29") (pinfunction "G3P_29") (pintype "output"))
    )
    (net (code "20") (name "/G3S") (class "Default")
      (node (ref "R3F") (pin "2") (pinfunction "2_2") (pintype "passive"))
      (node (ref "U1") (pin "7") (pinfunction "G3S_7") (pintype "output"))
    )
    (net (code "21") (name "/G4P") (class "Default")
      (node (ref "D4C") (pin "K") (pinfunction "C_K") (pintype "passive"))
      (node (ref "D4D") (pin "A") (pinfunction "A_A") (pintype "passive"))
      (node (ref "R4C") (pin "1") (pinfunction "1_1") (pintype "passive"))
      (node (ref "U1") (pin "32") (pinfunction "G4P_32") (pintype "output"))
    )
    (net (code "22") (name "/G4S") (class "Default")
      (node (ref "R4F") (pin "2") (pinfunction "2_2") (pintype "passive"))
      (node (ref "U1") (pin "5") (pinfunction "G4S_5") (pintype "output"))
    )
    (net (code "23") (name "/G5P") (class "Default")
      (node (ref "D5C") (pin "K") (pinfunction "C_K") (pintype "passive"))
      (node (ref "D5D") (pin "A") (pinfunction "A_A") (pintype "passive"))
      (node (ref "R5C") (pin "1") (pinfunction "1_1") (pintype "passive"))
      (node (ref "U1") (pin "35") (pinfunction "G5P_35") (pintype "output"))
    )
    (net (code "24") (name "/G5S") (class "Default")
      (node (ref "R5F") (pin "2") (pinfunction "2_2") (pintype "passive"))
      (node (ref "U1") (pin "3") (pinfunction "G5S_3") (pintype "output"))
    )
    (net (code "25") (name "/G6P") (class "Default")
      (node (ref "D6C") (pin "K") (pinfunction "C_K") (pintype "passive"))
      (node (ref "D6D") (pin "A") (pinfunction "A_A") (pintype "passive"))
      (node (ref "R6C") (pin "1") (pinfunction "1_1") (pintype "passive"))
      (node (ref "U1") (pin "38") (pinfunction "G6P_38") (pintype "output"))
    )
    (net (code "26") (name "/G6S") (class "Default")
      (node (ref "R6F") (pin "2") (pinfunction "2_2") (pintype "passive"))
      (node (ref "U1") (pin "1") (pinfunction "G6S_1") (pintype "output"))
    )
    (net (code "27") (name "/G7P") (class "Default")
      (node (ref "U2") (pin "23") (pinfunction "G1P_23") (pintype "output"))
    )
    (net (code "28") (name "/G7S") (class "Default")
      (node (ref "U2") (pin "11") (pinfunction "G1S_11") (pintype "output"))
    )
    (net (code "29") (name "/G8P") (class "Default")
      (node (ref "U2") (pin "26") (pinfunction "G2P_26") (pintype "output"))
    )
    (net (code "30") (name "/G8S") (class "Default")
      (node (ref "U2") (pin "9") (pinfunction "G2S_9") (pintype "output"))
    )
    (net (code "31") (name "/G9P") (class "Default")
      (node (ref "D9C") (pin "K") (pinfunction "C_K") (pintype "passive"))
      (node (ref "D9D") (pin "A") (pinfunction "A_A") (pintype "passive"))
      (node (ref "R9C") (pin "1") (pinfunction "1_1") (pintype "passive"))
      (node (ref "U2") (pin "29") (pinfunction "G3P_29") (pintype "output"))
    )
    (net (code "32") (name "/G9S") (class "Default")
      (node (ref "R9F") (pin "2") (pinfunction "2_2") (pintype "passive"))
      (node (ref "U2") (pin "7") (pinfunction "G3S_7") (pintype "output"))
    )
    (net (code "33") (name "/G10P") (class "Default")
      (node (ref "D10C") (pin "K") (pinfunction "C_K") (pintype "passive"))
      (node (ref "D10D") (pin "A") (pinfunction "A_A") (pintype "passive"))
      (node (ref "R10C") (pin "1") (pinfunction "1_1") (pintype "passive"))
      (node (ref "U2") (pin "32") (pinfunction "G4P_32") (pintype "output"))
    )
    (net (code "34") (name "/G10S") (class "Default")
      (node (ref "R10F") (pin "2") (pinfunction "2_2") (pintype "passive"))
      (node (ref "U2") (pin "5") (pinfunction "G4S_5") (pintype "output"))
    )
    (net (code "35") (name "/G11P") (class "Default")
      (node (ref "D11C") (pin "K") (pinfunction "C_K") (pintype "passive"))
      (node (ref "D11D") (pin "A") (pinfunction "A_A") (pintype "passive"))
      (node (ref "R11C") (pin "1") (pinfunction "1_1") (pintype "passive"))
      (node (ref "U2") (pin "35") (pinfunction "G5P_35") (pintype "output"))
    )
    (net (code "36") (name "/G11S") (class "Default")
      (node (ref "R11F") (pin "2") (pinfunction "2_2") (pintype "passive"))
      (node (ref "U2") (pin "3") (pinfunction "G5S_3") (pintype "output"))
    )
    (net (code "37") (name "/G12P") (class "Default")
      (node (ref "D12C") (pin "K") (pinfunction "C_K") (pintype "passive"))
      (node (ref "D12D") (pin "A") (pinfunction "A_A") (pintype "passive"))
      (node (ref "R12C") (pin "1") (pinfunction "1_1") (pintype "passive"))
      (node (ref "U2") (pin "38") (pinfunction "G6P_38") (pintype "output"))
    )
    (net (code "38") (name "/G12S") (class "Default")
      (node (ref "R12F") (pin "2") (pinfunction "2_2") (pintype "passive"))
      (node (ref "U2") (pin "1") (pinfunction "G6S_1") (pintype "output"))
    )
    (net (code "39") (name "/I1P") (class "Default")
      (node (ref "U1") (pin "22") (pinfunction "I1P_22") (pintype "input"))
    )
    (net (code "40") (name "/I1S") (class "Default")
      (node (ref "U1") (pin "12") (pinfunction "I1S_12") (pintype "input"))
    )
    (net (code "41") (name "/I2P") (class "Default")
      (node (ref "U1") (pin "25") (pinfunction "I2P_25") (pintype "input"))
    )
    (net (code "42") (name "/I2S") (class "Default")
      (node (ref "U1") (pin "10") (pinfunction "I2S_10") (pintype "input"))
    )
    (net (code "43") (name "/I3P") (class "Default")
      (node (ref "C3G") (pin "1") (pinfunction "1_1") (pintype "passive"))
      (node (ref "R3G") (pin "1") (pinfunction "1_1") (pintype "passive"))
      (node (ref "U1") (pin "28") (pinfunction "I3P_28") (pintype "input"))
    )
    (net (code "44") (name "/I3S") (class "Default")
      (node (ref "C3H") (pin "2") (pinfunction "2_2") (pintype "passive"))
      (node (ref "R3H") (pin "2") (pinfunction "2_2") (pintype "passive"))
      (node (ref "U1") (pin "8") (pinfunction "I3S_8") (pintype "input"))
    )
    (net (code "45") (name "/I4P") (class "Default")
      (node (ref "C4G") (pin "1") (pinfunction "1_1") (pintype "passive"))
      (node (ref "R4G") (pin "1") (pinfunction "1_1") (pintype "passive"))
      (node (ref "U1") (pin "31") (pinfunction "I4P_31") (pintype "input"))
    )
    (net (code "46") (name "/I4S") (class "Default")
      (node (ref "C4H") (pin "2") (pinfunction "2_2") (pintype "passive"))
      (node (ref "R4H") (pin "2") (pinfunction "2_2") (pintype "passive"))
      (node (ref "U1") (pin "6") (pinfunction "I4S_6") (pintype "input"))
    )
    (net (code "47") (name "/I5P") (class "Default")
      (node (ref "C5G") (pin "1") (pinfunction "1_1") (pintype "passive"))
      (node (ref "R5G") (pin "1") (pinfunction "1_1") (pintype "passive"))
      (node (ref "U1") (pin "34") (pinfunction "I5P_34") (pintype "input"))
    )
    (net (code "48") (name "/I5S") (class "Default")
      (node (ref "C5H") (pin "2") (pinfunction "2_2") (pintype "passive"))
      (node (ref "R5H") (pin "2") (pinfunction "2_2") (pintype "passive"))
      (node (ref "U1") (pin "4") (pinfunction "I5S_4") (pintype "input"))
    )
    (net (code "49") (name "/I6P") (class "Default")
      (node (ref "C6G") (pin "1") (pinfunction "1_1") (pintype "passive"))
      (node (ref "R6G") (pin "1") (pinfunction "1_1") (pintype "passive"))
      (node (ref "U1") (pin "37") (pinfunction "I6P_37") (pintype "input"))
    )
    (net (code "50") (name "/I6S") (class "Default")
      (node (ref "C6H") (pin "2") (pinfunction "2_2") (pintype "passive"))
      (node (ref "R6H") (pin "2") (pinfunction "2_2") (pintype "passive"))
      (node (ref "U1") (pin "2") (pinfunction "I6C_2") (pintype "input"))
    )
    (net (code "51") (name "/I7P") (class "Default")
      (node (ref "U2") (pin "22") (pinfunction "I1P_22") (pintype "input"))
    )
    (net (code "52") (name "/I7S") (class "Default")
      (node (ref "U2") (pin "12") (pinfunction "I1S_12") (pintype "input"))
    )
    (net (code "53") (name "/I8P") (class "Default")
      (node (ref "U2") (pin "25") (pinfunction "I2P_25") (pintype "input"))
    )
    (net (code "54") (name "/I8S") (class "Default")
      (node (ref "U2") (pin "10") (pinfunction "I2S_10") (pintype "input"))
    )
    (net (code "55") (name "/I9P") (class "Default")
      (node (ref "C9G") (pin "1") (pinfunction "1_1") (pintype "passive"))
      (node (ref "R9G") (pin "1") (pinfunction "1_1") (pintype "passive"))
      (node (ref "U2") (pin "28") (pinfunction "I3P_28") (pintype "input"))
    )
    (net (code "56") (name "/I9S") (class "Default")
      (node (ref "C9H") (pin "2") (pinfunction "2_2") (pintype "passive"))
      (node (ref "R9H") (pin "2") (pinfunction "2_2") (pintype "passive"))
      (node (ref "U2") (pin "8") (pinfunction "I3S_8") (pintype "input"))
    )
    (net (code "57") (name "/I10P") (class "Default")
      (node (ref "C10G") (pin "1") (pinfunction "1_1") (pintype "passive"))
      (node (ref "R10G") (pin "1") (pinfunction "1_1") (pintype "passive"))
      (node (ref "U2") (pin "31") (pinfunction "I4P_31") (pintype "input"))
    )
    (net (code "58") (name "/I10S") (class "Default")
      (node (ref "C10H") (pin "2") (pinfunction "2_2") (pintype "passive"))
      (node (ref "R10H") (pin "2") (pinfunction "2_2") (pintype "passive"))
      (node (ref "U2") (pin "6") (pinfunction "I4S_6") (pintype "input"))
    )
    (net (code "59") (name "/I11P") (class "Default")
      (node (ref "C11G") (pin "1") (pinfunction "1_1") (pintype "passive"))
      (node (ref "R11G") (pin "1") (pinfunction "1_1") (pintype "passive"))
      (node (ref "U2") (pin "34") (pinfunction "I5P_34") (pintype "input"))
    )
    (net (code "60") (name "/I11S") (class "Default")
      (node (ref "C11H") (pin "2") (pinfunction "2_2") (pintype "passive"))
      (node (ref "R11H") (pin "2") (pinfunction "2_2") (pintype "passive"))
      (node (ref "U2") (pin "4") (pinfunction "I5S_4") (pintype "input"))
    )
    (net (code "61") (name "/I12P") (class "Default")
      (node (ref "C12G") (pin "1") (pinfunction "1_1") (pintype "passive"))
      (node (ref "R12G") (pin "1") (pinfunction "1_1") (pintype "passive"))
      (node (ref "U2") (pin "37") (pinfunction "I6P_37") (pintype "input"))
    )
    (net (code "62") (name "/I12S") (class "Default")
      (node (ref "C12H") (pin "2") (pinfunction "2_2") (pintype "passive"))
      (node (ref "R12H") (pin "2") (pinfunction "2_2") (pintype "passive"))
      (node (ref "U2") (pin "2") (pinfunction "I6C_2") (pintype "input"))
    )
    (net (code "63") (name "/RTONP") (class "Default")
      (node (ref "R20") (pin "2") (pinfunction "2_2") (pintype "passive"))
      (node (ref "U1") (pin "14") (pinfunction "RTONP_14") (pintype "passive"))
    )
    (net (code "64") (name "/RTONS") (class "Default")
      (node (ref "R19") (pin "2") (pinfunction "2_2") (pintype "passive"))
      (node (ref "U1") (pin "13") (pinfunction "RTONS_13") (pintype "passive"))
    )
    (net (code "65") (name "/SCKI") (class "Default")
      (node (ref "COMM") (pin "2") (pinfunction "2_2") (pintype "passive"))
      (node (ref "U1") (pin "17") (pinfunction "SCKI_17") (pintype "input"))
    )
    (net (code "66") (name "/SCKO") (class "Default")
      (node (ref "D6") (pin "C") (pinfunction "C_C") (pintype "passive"))
      (node (ref "U1") (pin "44") (pinfunction "SCKO_44") (pintype "output"))
    )
    (net (code "67") (name "/SDIO") (class "Default")
      (node (ref "COMM") (pin "1") (pinfunction "1_1") (pintype "passive"))
      (node (ref "U1") (pin "18") (pinfunction "SDI_18") (pintype "input"))
      (node (ref "U1") (pin "19") (pinfunction "SDO_19") (pintype "output"))
    )
    (net (code "68") (name "/SDOI") (class "Default")
      (node (ref "D7") (pin "C") (pinfunction "C_C") (pintype "passive"))
      (node (ref "U1") (pin "43") (pinfunction "SDOI_43") (pintype "bidirectional"))
    )
    (net (code "69") (name "/TOP6_TS") (class "Default")
      (node (ref "C10F") (pin "2") (pinfunction "2_2") (pintype "passive"))
      (node (ref "C10R") (pin "1") (pinfunction "1_1") (pintype "passive"))
      (node (ref "C11F") (pin "2") (pinfunction "2_2") (pintype "passive"))
      (node (ref "C11R") (pin "1") (pinfunction "1_1") (pintype "passive"))
      (node (ref "C12F") (pin "2") (pinfunction "2_2") (pintype "passive"))
      (node (ref "C12R") (pin "1") (pinfunction "1_1") (pintype "passive"))
      (node (ref "C9F") (pin "2") (pinfunction "2_2") (pintype "passive"))
      (node (ref "C9R") (pin "1") (pinfunction "1_1") (pintype "passive"))
      (node (ref "E15") (pin "1") (pinfunction "1_1") (pintype "passive"))
      (node (ref "F14") (pin "2") (pinfunction "2_2") (pintype "bidirectional"))
      (node (ref "R8") (pin "1") (pinfunction "1_1") (pintype "passive"))
      (node (ref "T10") (pin "7") (pinfunction "7_7") (pintype "passive"))
      (node (ref "T11") (pin "7") (pinfunction "7_7") (pintype "passive"))
      (node (ref "T12") (pin "7") (pinfunction "7_7") (pintype "passive"))
      (node (ref "T9") (pin "7") (pinfunction "7_7") (pintype "passive"))
    )
    (net (code "70") (name "/V-") (class "Default")
      (node (ref "C1") (pin "2") (pinfunction "2_2") (pintype "passive"))
      (node (ref "C11") (pin "2") (pinfunction "2_2") (pintype "passive"))
      (node (ref "C12") (pin "2") (pinfunction "2_2") (pintype "passive"))
      (node (ref "C2") (pin "2") (pinfunction "2_2") (pintype "passive"))
      (node (ref "C3A") (pin "2") (pinfunction "2_2") (pintype "passive"))
      (node (ref "C3B") (pin "2") (pinfunction "2_2") (pintype "passive"))
      (node (ref "C3G") (pin "2") (pinfunction "2_2") (pintype "passive"))
      (node (ref "C3H") (pin "1") (pinfunction "1_1") (pintype "passive"))
      (node (ref "C3K") (pin "2") (pinfunction "2_2") (pintype "passive"))
      (node (ref "C3R") (pin "2") (pinfunction "2_2") (pintype "passive"))
      (node (ref "C4H") (pin "1") (pinfunction "1_1") (pintype "passive"))
      (node (ref "C4R") (pin "2") (pinfunction "2_2") (pintype "passive"))
      (node (ref "C5H") (pin "1") (pinfunction "1_1") (pintype "passive"))
      (node (ref "C5R") (pin "2") (pinfunction "2_2") (pintype "passive"))
      (node (ref "C6H") (pin "1") (pinfunction "1_1") (pintype "passive"))
      (node (ref "C6R") (pin "2") (pinfunction "2_2") (pintype "passive"))
      (node (ref "COMM") (pin "4") (pinfunction "4_4") (pintype "passive"))
      (node (ref "D3C") (pin "A") (pinfunction "A_A") (pintype "passive"))
      (node (ref "D3E") (pin "P$2") (pinfunction "P$1_P$2") (pintype "bidirectional"))
      (node (ref "D3E") (pin "P$3") (pinfunction "P$2_P$3") (pintype "bidirectional"))
      (node (ref "E1") (pin "1") (pinfunction "1_1") (pintype "passive"))
      (node (ref "F15") (pin "1") (pinfunction "1_1") (pintype "bidirectional"))
      (node (ref "R19") (pin "1") (pinfunction "1_1") (pintype "passive"))
      (node (ref "R20") (pin "1") (pinfunction "1_1") (pintype "passive"))
      (node (ref "R3J") (pin "1") (pinfunction "1_1") (pintype "passive"))
      (node (ref "RS3A") (pin "1") (pinfunction "1_1") (pintype "passive"))
      (node (ref "RS3B") (pin "1") (pinfunction "1_1") (pintype "passive"))
      (node (ref "RS4B") (pin "1") (pinfunction "1_1") (pintype "passive"))
      (node (ref "RS5B") (pin "1") (pinfunction "1_1") (pintype "passive"))
      (node (ref "RS6B") (pin "1") (pinfunction "1_1") (pintype "passive"))
      (node (ref "U1") (pin "15") (pinfunction "CTRL_15") (pintype "input"))
      (node (ref "U1") (pin "21") (pinfunction "V-_2_21") (pintype "power_in"))
      (node (ref "U1") (pin "24") (pinfunction "C1_24") (pintype "power_in"))
      (node (ref "U1") (pin "27") (pinfunction "C2_27") (pintype "power_in"))
      (node (ref "U1") (pin "47") (pinfunction "TOS_47") (pintype "input"))
      (node (ref "U1") (pin "49") (pinfunction "V-_49") (pintype "power_in"))
      (node (ref "VOLT_TAPS") (pin "1") (pinfunction "1_1") (pintype "passive"))
    )
    (net (code "71") (name "/VREG") (class "Default")
      (node (ref "C1") (pin "1") (pinfunction "1_1") (pintype "passive"))
      (node (ref "C2") (pin "1") (pinfunction "1_1") (pintype "passive"))
      (node (ref "Q1") (pin "1") (pinfunction "G_1") (pintype "passive"))
      (node (ref "R1") (pin "2") (pinfunction "2_2") (pintype "passive"))
      (node (ref "U1") (pin "42") (pinfunction "BOOST_42") (pintype "input"))
      (node (ref "U1") (pin "46") (pinfunction "VMODE_46") (pintype "input"))
      (node (ref "U1") (pin "48") (pinfunction "VREG_48") (pintype "power_in"))
    )
    (net (code "72") (name "/VREG2") (class "Default")
      (node (ref "C5") (pin "2") (pinfunction "2_2") (pintype "passive"))
      (node (ref "C6") (pin "2") (pinfunction "2_2") (pintype "passive"))
      (node (ref "Q2") (pin "1") (pinfunction "G_1") (pintype "passive"))
      (node (ref "Q5") (pin "2") (pinfunction "S_2") (pintype "passive"))
      (node (ref "R53") (pin "1") (pinfunction "1_1") (pintype "passive"))
      (node (ref "R7") (pin "1") (pinfunction "1_1") (pintype "passive"))
      (node (ref "U2") (pin "42") (pinfunction "BOOST_42") (pintype "input"))
      (node (ref "U2") (pin "47") (pinfunction "TOS_47") (pintype "input"))
      (node (ref "U2") (pin "48") (pinfunction "VREG_48") (pintype "power_in"))
    )
    (net (code "73") (name "/WDTA") (class "Default")
      (node (ref "Q1") (pin "2") (pinfunction "S_2") (pintype "passive"))
      (node (ref "R1") (pin "1") (pinfunction "1_1") (pintype "passive"))
      (node (ref "U1") (pin "20") (pinfunction "WDT_20") (pintype "output"))
      (node (ref "WDTA") (pin "1") (pinfunction "1_1") (pintype "passive"))
    )
    (net (code "74") (name "/WDTC") (class "Default")
      (node (ref "Q2") (pin "2") (pinfunction "S_2") (pintype "passive"))
      (node (ref "R7") (pin "2") (pinfunction "2_2") (pintype "passive"))
      (node (ref "U2") (pin "20") (pinfunction "WDT_20") (pintype "output"))
      (node (ref "WDTC") (pin "1") (pinfunction "1_1") (pintype "passive"))
    )
    (net (code "75") (name "Net-(BATT-Pad2)") (class "Default")
      (node (ref "BATT") (pin "2") (pinfunction "2_2") (pintype "passive"))
      (node (ref "F11") (pin "1") (pinfunction "1_1") (pintype "bidirectional"))
    )
    (net (code "76") (name "Net-(BATT-Pad3)") (class "Default")
      (node (ref "BATT") (pin "3") (pinfunction "3_3") (pintype "passive"))
      (node (ref "F10") (pin "2") (pinfunction "2_2") (pintype "bidirectional"))
    )
    (net (code "77") (name "Net-(BATT-Pad4)") (class "Default")
      (node (ref "BATT") (pin "4") (pinfunction "4_4") (pintype "passive"))
      (node (ref "F9") (pin "1") (pinfunction "1_1") (pintype "bidirectional"))
    )
    (net (code "78") (name "Net-(BATT-Pad5)") (class "Default")
      (node (ref "BATT") (pin "5") (pinfunction "5_5") (pintype "passive"))
      (node (ref "F6") (pin "2") (pinfunction "2_2") (pintype "bidirectional"))
    )
    (net (code "79") (name "Net-(BATT-Pad6)") (class "Default")
      (node (ref "BATT") (pin "6") (pinfunction "6_6") (pintype "passive"))
      (node (ref "F5") (pin "1") (pinfunction "1_1") (pintype "bidirectional"))
    )
    (net (code "80") (name "Net-(BATT-Pad7)") (class "Default")
      (node (ref "BATT") (pin "7") (pinfunction "7_7") (pintype "passive"))
      (node (ref "F4") (pin "2") (pinfunction "2_2") (pintype "bidirectional"))
    )
    (net (code "81") (name "Net-(BATT-Pad8)") (class "Default")
      (node (ref "BATT") (pin "8") (pinfunction "8_8") (pintype "passive"))
      (node (ref "F3") (pin "1") (pinfunction "1_1") (pintype "bidirectional"))
    )
    (net (code "82") (name "Net-(BATT-Pad9)") (class "Default")
      (node (ref "BATT") (pin "9") (pinfunction "9_9") (pintype "passive"))
      (node (ref "F15") (pin "2") (pinfunction "2_2") (pintype "bidirectional"))
    )
    (net (code "83") (name "Net-(C3E-Pad2)") (class "Default")
      (node (ref "C3E") (pin "2") (pinfunction "2_2") (pintype "passive"))
      (node (ref "R3A") (pin "1") (pinfunction "1_1") (pintype "passive"))
    )
    (net (code "84") (name "Net-(C3F-Pad1)") (class "Default")
      (node (ref "C3F") (pin "1") (pinfunction "1_1") (pintype "passive"))
      (node (ref "R3B") (pin "2") (pinfunction "2_2") (pintype "passive"))
    )
    (net (code "85") (name "Net-(C4E-Pad2)") (class "Default")
      (node (ref "C4E") (pin "2") (pinfunction "2_2") (pintype "passive"))
      (node (ref "R4A") (pin "1") (pinfunction "1_1") (pintype "passive"))
    )
    (net (code "86") (name "Net-(C4F-Pad1)") (class "Default")
      (node (ref "C4F") (pin "1") (pinfunction "1_1") (pintype "passive"))
      (node (ref "R4B") (pin "2") (pinfunction "2_2") (pintype "passive"))
    )
    (net (code "87") (name "Net-(C5E-Pad2)") (class "Default")
      (node (ref "C5E") (pin "2") (pinfunction "2_2") (pintype "passive"))
      (node (ref "R5A") (pin "1") (pinfunction "1_1") (pintype "passive"))
    )
    (net (code "88") (name "Net-(C5F-Pad1)") (class "Default")
      (node (ref "C5F") (pin "1") (pinfunction "1_1") (pintype "passive"))
      (node (ref "R5B") (pin "2") (pinfunction "2_2") (pintype "passive"))
    )
    (net (code "89") (name "Net-(C6E-Pad2)") (class "Default")
      (node (ref "C6E") (pin "2") (pinfunction "2_2") (pintype "passive"))
      (node (ref "R6A") (pin "1") (pinfunction "1_1") (pintype "passive"))
    )
    (net (code "90") (name "Net-(C6F-Pad1)") (class "Default")
      (node (ref "C6F") (pin "1") (pinfunction "1_1") (pintype "passive"))
      (node (ref "R6B") (pin "2") (pinfunction "2_2") (pintype "passive"))
    )
    (net (code "91") (name "Net-(C9-Pad1)") (class "Default")
      (node (ref "C9") (pin "1") (pinfunction "1_1") (pintype "passive"))
      (node (ref "R11") (pin "1") (pinfunction "1_1") (pintype "passive"))
    )
    (net (code "92") (name "Net-(C9E-Pad2)") (class "Default")
      (node (ref "C9E") (pin "2") (pinfunction "2_2") (pintype "passive"))
      (node (ref "R9A") (pin "1") (pinfunction "1_1") (pintype "passive"))
    )
    (net (code "93") (name "Net-(C9F-Pad1)") (class "Default")
      (node (ref "C9F") (pin "1") (pinfunction "1_1") (pintype "passive"))
      (node (ref "R9B") (pin "2") (pinfunction "2_2") (pintype "passive"))
    )
    (net (code "94") (name "Net-(C10E-Pad2)") (class "Default")
      (node (ref "C10E") (pin "2") (pinfunction "2_2") (pintype "passive"))
      (node (ref "R10A") (pin "1") (pinfunction "1_1") (pintype "passive"))
    )
    (net (code "95") (name "Net-(C10F-Pad1)") (class "Default")
      (node (ref "C10F") (pin "1") (pinfunction "1_1") (pintype "passive"))
      (node (ref "R10B") (pin "2") (pinfunction "2_2") (pintype "passive"))
    )
    (net (code "96") (name "Net-(C11-Pad1)") (class "Default")
      (node (ref "C11") (pin "1") (pinfunction "1_1") (pintype "passive"))
      (node (ref "R12") (pin "1") (pinfunction "1_1") (pintype "passive"))
    )
    (net (code "97") (name "Net-(C11E-Pad2)") (class "Default")
      (node (ref "C11E") (pin "2") (pinfunction "2_2") (pintype "passive"))
      (node (ref "R11A") (pin "1") (pinfunction "1_1") (pintype "passive"))
    )
    (net (code "98") (name "Net-(C11F-Pad1)") (class "Default")
      (node (ref "C11F") (pin "1") (pinfunction "1_1") (pintype "passive"))
      (node (ref "R11B") (pin "2") (pinfunction "2_2") (pintype "passive"))
    )
    (net (code "99") (name "Net-(C12E-Pad2)") (class "Default")
      (node (ref "C12E") (pin "2") (pinfunction "2_2") (pintype "passive"))
      (node (ref "R12A") (pin "1") (pinfunction "1_1") (pintype "passive"))
    )
    (net (code "100") (name "Net-(C12F-Pad1)") (class "Default")
      (node (ref "C12F") (pin "1") (pinfunction "1_1") (pintype "passive"))
      (node (ref "R12B") (pin "2") (pinfunction "2_2") (pintype "passive"))
    )
    (net (code "101") (name "Net-(C15-Pad1)") (class "Default")
      (node (ref "C15") (pin "1") (pinfunction "1_1") (pintype "passive"))
      (node (ref "R15") (pin "1") (pinfunction "1_1") (pintype "passive"))
    )
    (net (code "102") (name "Net-(C17-Pad1)") (class "Default")
      (node (ref "C17") (pin "1") (pinfunction "1_1") (pintype "passive"))
      (node (ref "R16") (pin "1") (pinfunction "1_1") (pintype "passive"))
    )
    (net (code "103") (name "Net-(D1-A)") (class "Default")
      (node (ref "C3") (pin "1") (pinfunction "1_1") (pintype "passive"))
      (node (ref "D1") (pin "2") (pinfunction "A_2") (pintype "passive"))
      (node (ref "D2") (pin "1") (pinfunction "C_1") (pintype "passive"))
    )
    (net (code "104") (name "Net-(D2-A)") (class "Default")
      (node (ref "D2") (pin "2") (pinfunction "A_2") (pintype "passive"))
      (node (ref "R6") (pin "2") (pinfunction "2_2") (pintype "passive"))
    )
    (net (code "105") (name "Net-(D3-A)") (class "Default")
      (node (ref "C7") (pin "2") (pinfunction "2_2") (pintype "passive"))
      (node (ref "D3") (pin "2") (pinfunction "A_2") (pintype "passive"))
      (node (ref "D4") (pin "1") (pinfunction "C_1") (pintype "passive"))
    )
    (net (code "106") (name "Net-(D3-C)") (class "Default")
      (node (ref "C8") (pin "1") (pinfunction "1_1") (pintype "passive"))
      (node (ref "D3") (pin "1") (pinfunction "C_1") (pintype "passive"))
      (node (ref "U2") (pin "40") (pinfunction "BOOST+_40") (pintype "power_in"))
    )
    (net (code "107") (name "Net-(D3A-1)") (class "Default")
      (node (ref "D3A") (pin "2") (pinfunction "1_2") (pintype "passive"))
      (node (ref "Q3A") (pin "5") (pinfunction "5_5") (pintype "passive"))
      (node (ref "Q3A") (pin "6") (pinfunction "6_6") (pintype "passive"))
      (node (ref "Q3A") (pin "7") (pinfunction "7_7") (pintype "passive"))
      (node (ref "Q3A") (pin "8") (pinfunction "8_8") (pintype "passive"))
      (node (ref "Q3A") (pin "9") (pinfunction "8_9") (pintype "passive"))
      (node (ref "R3A") (pin "2") (pinfunction "2_2") (pintype "passive"))
      (node (ref "T3") (pin "10") (pinfunction "10_10") (pintype "passive"))
      (node (ref "T3") (pin "9") (pinfunction "9_9") (pintype "passive"))
    )
    (net (code "108") (name "Net-(D3A-2)") (class "Default")
      (node (ref "D3A") (pin "1") (pinfunction "2_1") (pintype "passive"))
      (node (ref "Q3A") (pin "1") (pinfunction "1_1") (pintype "passive"))
      (node (ref "Q3A") (pin "2") (pinfunction "2_2") (pintype "passive"))
      (node (ref "Q3A") (pin "3") (pinfunction "3_3") (pintype "passive"))
      (node (ref "R3G") (pin "2") (pinfunction "2_2") (pintype "passive"))
      (node (ref "RS3A") (pin "2") (pinfunction "2_2") (pintype "passive"))
    )
    (net (code "109") (name "Net-(D3B-PadA)") (class "Default")
      (node (ref "D3B") (pin "A") (pinfunction "A_A") (pintype "passive"))
      (node (ref "Q3B") (pin "1") (pinfunction "S_1") (pintype "passive"))
      (node (ref "Q3B") (pin "2") (pinfunction "S_2") (pintype "passive"))
      (node (ref "Q3B") (pin "3") (pinfunction "S_3") (pintype "passive"))
      (node (ref "R3H") (pin "1") (pinfunction "1_1") (pintype "passive"))
      (node (ref "RS3B") (pin "2") (pinfunction "2_2") (pintype "passive"))
    )
    (net (code "110") (name "Net-(D3B-PadK)") (class "Default")
      (node (ref "D3B") (pin "K") (pinfunction "K_K") (pintype "passive"))
      (node (ref "Q3B") (pin "5") (pinfunction "D_5") (pintype "passive"))
      (node (ref "Q3B") (pin "6") (pinfunction "D_6") (pintype "passive"))
      (node (ref "Q3B") (pin "7") (pinfunction "D_7") (pintype "passive"))
      (node (ref "Q3B") (pin "8") (pinfunction "D_8") (pintype "passive"))
      (node (ref "Q3B") (pin "9") (pinfunction "D_9") (pintype "passive"))
      (node (ref "R3B") (pin "1") (pinfunction "1_1") (pintype "passive"))
      (node (ref "T3") (pin "5") (pinfunction "5_5") (pintype "passive"))
    )
    (net (code "111") (name "Net-(D3D-PadC)") (class "Default")
      (node (ref "D3D") (pin "C") (pinfunction "C_C") (pintype "passive"))
      (node (ref "R3J") (pin "2") (pinfunction "2_2") (pintype "passive"))
    )
    (net (code "112") (name "Net-(D4-A)") (class "Default")
      (node (ref "D4") (pin "2") (pinfunction "A_2") (pintype "passive"))
      (node (ref "R10") (pin "1") (pinfunction "1_1") (pintype "passive"))
    )
    (net (code "113") (name "Net-(D4A-1)") (class "Default")
      (node (ref "D4A") (pin "2") (pinfunction "1_2") (pintype "passive"))
      (node (ref "Q4A") (pin "5") (pinfunction "5_5") (pintype "passive"))
      (node (ref "Q4A") (pin "6") (pinfunction "6_6") (pintype "passive"))
      (node (ref "Q4A") (pin "7") (pinfunction "7_7") (pintype "passive"))
      (node (ref "Q4A") (pin "8") (pinfunction "8_8") (pintype "passive"))
      (node (ref "Q4A") (pin "9") (pinfunction "8_9") (pintype "passive"))
      (node (ref "R4A") (pin "2") (pinfunction "2_2") (pintype "passive"))
      (node (ref "T4") (pin "10") (pinfunction "10_10") (pintype "passive"))
      (node (ref "T4") (pin "9") (pinfunction "9_9") (pintype "passive"))
    )
    (net (code "114") (name "Net-(D4A-2)") (class "Default")
      (node (ref "D4A") (pin "1") (pinfunction "2_1") (pintype "passive"))
      (node (ref "Q4A") (pin "1") (pinfunction "1_1") (pintype "passive"))
      (node (ref "Q4A") (pin "2") (pinfunction "2_2") (pintype "passive"))
      (node (ref "Q4A") (pin "3") (pinfunction "3_3") (pintype "passive"))
      (node (ref "R4G") (pin "2") (pinfunction "2_2") (pintype "passive"))
      (node (ref "RS4A") (pin "2") (pinfunction "2_2") (pintype "passive"))
    )
    (net (code "115") (name "Net-(D4B-PadA)") (class "Default")
      (node (ref "D4B") (pin "A") (pinfunction "A_A") (pintype "passive"))
      (node (ref "Q4B") (pin "1") (pinfunction "S_1") (pintype "passive"))
      (node (ref "Q4B") (pin "2") (pinfunction "S_2") (pintype "passive"))
      (node (ref "Q4B") (pin "3") (pinfunction "S_3") (pintype "passive"))
      (node (ref "R4H") (pin "1") (pinfunction "1_1") (pintype "passive"))
      (node (ref "RS4B") (pin "2") (pinfunction "2_2") (pintype "passive"))
    )
    (net (code "116") (name "Net-(D4B-PadK)") (class "Default")
      (node (ref "D4B") (pin "K") (pinfunction "K_K") (pintype "passive"))
      (node (ref "Q4B") (pin "5") (pinfunction "D_5") (pintype "passive"))
      (node (ref "Q4B") (pin "6") (pinfunction "D_6") (pintype "passive"))
      (node (ref "Q4B") (pin "7") (pinfunction "D_7") (pintype "passive"))
      (node (ref "Q4B") (pin "8") (pinfunction "D_8") (pintype "passive"))
      (node (ref "Q4B") (pin "9") (pinfunction "D_9") (pintype "passive"))
      (node (ref "R4B") (pin "1") (pinfunction "1_1") (pintype "passive"))
      (node (ref "T4") (pin "5") (pinfunction "5_5") (pintype "passive"))
    )
    (net (code "117") (name "Net-(D4D-PadC)") (class "Default")
      (node (ref "D4D") (pin "C") (pinfunction "C_C") (pintype "passive"))
      (node (ref "R4J") (pin "2") (pinfunction "2_2") (pintype "passive"))
    )
    (net (code "118") (name "Net-(D5A-1)") (class "Default")
      (node (ref "D5A") (pin "2") (pinfunction "1_2") (pintype "passive"))
      (node (ref "Q5A") (pin "5") (pinfunction "5_5") (pintype "passive"))
      (node (ref "Q5A") (pin "6") (pinfunction "6_6") (pintype "passive"))
      (node (ref "Q5A") (pin "7") (pinfunction "7_7") (pintype "passive"))
      (node (ref "Q5A") (pin "8") (pinfunction "8_8") (pintype "passive"))
      (node (ref "Q5A") (pin "9") (pinfunction "8_9") (pintype "passive"))
      (node (ref "R5A") (pin "2") (pinfunction "2_2") (pintype "passive"))
      (node (ref "T5") (pin "10") (pinfunction "10_10") (pintype "passive"))
      (node (ref "T5") (pin "9") (pinfunction "9_9") (pintype "passive"))
    )
    (net (code "119") (name "Net-(D5A-2)") (class "Default")
      (node (ref "D5A") (pin "1") (pinfunction "2_1") (pintype "passive"))
      (node (ref "Q5A") (pin "1") (pinfunction "1_1") (pintype "passive"))
      (node (ref "Q5A") (pin "2") (pinfunction "2_2") (pintype "passive"))
      (node (ref "Q5A") (pin "3") (pinfunction "3_3") (pintype "passive"))
      (node (ref "R5G") (pin "2") (pinfunction "2_2") (pintype "passive"))
      (node (ref "RS5A") (pin "2") (pinfunction "2_2") (pintype "passive"))
    )
    (net (code "120") (name "Net-(D5B-PadA)") (class "Default")
      (node (ref "D5B") (pin "A") (pinfunction "A_A") (pintype "passive"))
      (node (ref "Q5B") (pin "1") (pinfunction "S_1") (pintype "passive"))
      (node (ref "Q5B") (pin "2") (pinfunction "S_2") (pintype "passive"))
      (node (ref "Q5B") (pin "3") (pinfunction "S_3") (pintype "passive"))
      (node (ref "R5H") (pin "1") (pinfunction "1_1") (pintype "passive"))
      (node (ref "RS5B") (pin "2") (pinfunction "2_2") (pintype "passive"))
    )
    (net (code "121") (name "Net-(D5B-PadK)") (class "Default")
      (node (ref "D5B") (pin "K") (pinfunction "K_K") (pintype "passive"))
      (node (ref "Q5B") (pin "5") (pinfunction "D_5") (pintype "passive"))
      (node (ref "Q5B") (pin "6") (pinfunction "D_6") (pintype "passive"))
      (node (ref "Q5B") (pin "7") (pinfunction "D_7") (pintype "passive"))
      (node (ref "Q5B") (pin "8") (pinfunction "D_8") (pintype "passive"))
      (node (ref "Q5B") (pin "9") (pinfunction "D_9") (pintype "passive"))
      (node (ref "R5B") (pin "1") (pinfunction "1_1") (pintype "passive"))
      (node (ref "T5") (pin "5") (pinfunction "5_5") (pintype "passive"))
    )
    (net (code "122") (name "Net-(D5D-PadC)") (class "Default")
      (node (ref "D5D") (pin "C") (pinfunction "C_C") (pintype "passive"))
      (node (ref "R5J") (pin "2") (pinfunction "2_2") (pintype "passive"))
    )
    (net (code "123") (name "Net-(D6A-1)") (class "Default")
      (node (ref "D6A") (pin "2") (pinfunction "1_2") (pintype "passive"))
      (node (ref "Q6A") (pin "5") (pinfunction "5_5") (pintype "passive"))
      (node (ref "Q6A") (pin "6") (pinfunction "6_6") (pintype "passive"))
      (node (ref "Q6A") (pin "7") (pinfunction "7_7") (pintype "passive"))
      (node (ref "Q6A") (pin "8") (pinfunction "8_8") (pintype "passive"))
      (node (ref "Q6A") (pin "9") (pinfunction "8_9") (pintype "passive"))
      (node (ref "R6A") (pin "2") (pinfunction "2_2") (pintype "passive"))
      (node (ref "T6") (pin "10") (pinfunction "10_10") (pintype "passive"))
      (node (ref "T6") (pin "9") (pinfunction "9_9") (pintype "passive"))
    )
    (net (code "124") (name "Net-(D6A-2)") (class "Default")
      (node (ref "D6A") (pin "1") (pinfunction "2_1") (pintype "passive"))
      (node (ref "Q6A") (pin "1") (pinfunction "1_1") (pintype "passive"))
      (node (ref "Q6A") (pin "2") (pinfunction "2_2") (pintype "passive"))
      (node (ref "Q6A") (pin "3") (pinfunction "3_3") (pintype "passive"))
      (node (ref "R6G") (pin "2") (pinfunction "2_2") (pintype "passive"))
      (node (ref "RS6A") (pin "2") (pinfunction "2_2") (pintype "passive"))
    )
    (net (code "125") (name "Net-(D6B-PadA)") (class "Default")
      (node (ref "D6B") (pin "A") (pinfunction "A_A") (pintype "passive"))
      (node (ref "Q6B") (pin "1") (pinfunction "S_1") (pintype "passive"))
      (node (ref "Q6B") (pin "2") (pinfunction "S_2") (pintype "passive"))
      (node (ref "Q6B") (pin "3") (pinfunction "S_3") (pintype "passive"))
      (node (ref "R6H") (pin "1") (pinfunction "1_1") (pintype "passive"))
      (node (ref "RS6B") (pin "2") (pinfunction "2_2") (pintype "passive"))
    )
    (net (code "126") (name "Net-(D6B-PadK)") (class "Default")
      (node (ref "D6B") (pin "K") (pinfunction "K_K") (pintype "passive"))
      (node (ref "Q6B") (pin "5") (pinfunction "D_5") (pintype "passive"))
      (node (ref "Q6B") (pin "6") (pinfunction "D_6") (pintype "passive"))
      (node (ref "Q6B") (pin "7") (pinfunction "D_7") (pintype "passive"))
      (node (ref "Q6B") (pin "8") (pinfunction "D_8") (pintype "passive"))
      (node (ref "Q6B") (pin "9") (pinfunction "D_9") (pintype "passive"))
      (node (ref "R6B") (pin "1") (pinfunction "1_1") (pintype "passive"))
      (node (ref "T6") (pin "5") (pinfunction "5_5") (pintype "passive"))
    )
    (net (code "127") (name "Net-(D6D-PadC)") (class "Default")
      (node (ref "D6D") (pin "C") (pinfunction "C_C") (pintype "passive"))
      (node (ref "R6J") (pin "2") (pinfunction "2_2") (pintype "passive"))
    )
    (net (code "128") (name "Net-(D8-PadC)") (class "Default")
      (node (ref "D8") (pin "C") (pinfunction "C_C") (pintype "passive"))
      (node (ref "R56") (pin "2") (pinfunction "2_2") (pintype "passive"))
    )
    (net (code "129") (name "Net-(D9-PadC)") (class "Default")
      (node (ref "D9") (pin "C") (pinfunction "C_C") (pintype "passive"))
      (node (ref "R54") (pin "2") (pinfunction "2_2") (pintype "passive"))
    )
    (net (code "130") (name "Net-(D9A-1)") (class "Default")
      (node (ref "D9A") (pin "2") (pinfunction "1_2") (pintype "passive"))
      (node (ref "Q9A") (pin "5") (pinfunction "5_5") (pintype "passive"))
      (node (ref "Q9A") (pin "6") (pinfunction "6_6") (pintype "passive"))
      (node (ref "Q9A") (pin "7") (pinfunction "7_7") (pintype "passive"))
      (node (ref "Q9A") (pin "8") (pinfunction "8_8") (pintype "passive"))
      (node (ref "Q9A") (pin "9") (pinfunction "8_9") (pintype "passive"))
      (node (ref "R9A") (pin "2") (pinfunction "2_2") (pintype "passive"))
      (node (ref "T9") (pin "10") (pinfunction "10_10") (pintype "passive"))
      (node (ref "T9") (pin "9") (pinfunction "9_9") (pintype "passive"))
    )
    (net (code "131") (name "Net-(D9A-2)") (class "Default")
      (node (ref "D9A") (pin "1") (pinfunction "2_1") (pintype "passive"))
      (node (ref "Q9A") (pin "1") (pinfunction "1_1") (pintype "passive"))
      (node (ref "Q9A") (pin "2") (pinfunction "2_2") (pintype "passive"))
      (node (ref "Q9A") (pin "3") (pinfunction "3_3") (pintype "passive"))
      (node (ref "R9G") (pin "2") (pinfunction "2_2") (pintype "passive"))
      (node (ref "RS9A") (pin "2") (pinfunction "2_2") (pintype "passive"))
    )
    (net (code "132") (name "Net-(D9B-PadA)") (class "Default")
      (node (ref "D9B") (pin "A") (pinfunction "A_A") (pintype "passive"))
      (node (ref "Q9B") (pin "1") (pinfunction "S_1") (pintype "passive"))
      (node (ref "Q9B") (pin "2") (pinfunction "S_2") (pintype "passive"))
      (node (ref "Q9B") (pin "3") (pinfunction "S_3") (pintype "passive"))
      (node (ref "R9H") (pin "1") (pinfunction "1_1") (pintype "passive"))
      (node (ref "RS9B") (pin "2") (pinfunction "2_2") (pintype "passive"))
    )
    (net (code "133") (name "Net-(D9B-PadK)") (class "Default")
      (node (ref "D9B") (pin "K") (pinfunction "K_K") (pintype "passive"))
      (node (ref "Q9B") (pin "5") (pinfunction "D_5") (pintype "passive"))
      (node (ref "Q9B") (pin "6") (pinfunction "D_6") (pintype "passive"))
      (node (ref "Q9B") (pin "7") (pinfunction "D_7") (pintype "passive"))
      (node (ref "Q9B") (pin "8") (pinfunction "D_8") (pintype "passive"))
      (node (ref "Q9B") (pin "9") (pinfunction "D_9") (pintype "passive"))
      (node (ref "R9B") (pin "1") (pinfunction "1_1") (pintype "passive"))
      (node (ref "T9") (pin "5") (pinfunction "5_5") (pintype "passive"))
    )
    (net (code "134") (name "Net-(D9D-PadC)") (class "Default")
      (node (ref "D9D") (pin "C") (pinfunction "C_C") (pintype "passive"))
      (node (ref "R9J") (pin "2") (pinfunction "2_2") (pintype "passive"))
    )
    (net (code "135") (name "Net-(D10-K)") (class "Default")
      (node (ref "D10") (pin "C") (pinfunction "K_C") (pintype "passive"))
      (node (ref "Q1") (pin "3") (pinfunction "D_3") (pintype "passive"))
      (node (ref "R4") (pin "1") (pinfunction "1_1") (pintype "passive"))
    )
    (net (code "136") (name "Net-(D10A-1)") (class "Default")
      (node (ref "D10A") (pin "2") (pinfunction "1_2") (pintype "passive"))
      (node (ref "Q10A") (pin "5") (pinfunction "5_5") (pintype "passive"))
      (node (ref "Q10A") (pin "6") (pinfunction "6_6") (pintype "passive"))
      (node (ref "Q10A") (pin "7") (pinfunction "7_7") (pintype "passive"))
      (node (ref "Q10A") (pin "8") (pinfunction "8_8") (pintype "passive"))
      (node (ref "Q10A") (pin "9") (pinfunction "8_9") (pintype "passive"))
      (node (ref "R10A") (pin "2") (pinfunction "2_2") (pintype "passive"))
      (node (ref "T10") (pin "10") (pinfunction "10_10") (pintype "passive"))
      (node (ref "T10") (pin "9") (pinfunction "9_9") (pintype "passive"))
    )
    (net (code "137") (name "Net-(D10A-2)") (class "Default")
      (node (ref "D10A") (pin "1") (pinfunction "2_1") (pintype "passive"))
      (node (ref "Q10A") (pin "1") (pinfunction "1_1") (pintype "passive"))
      (node (ref "Q10A") (pin "2") (pinfunction "2_2") (pintype "passive"))
      (node (ref "Q10A") (pin "3") (pinfunction "3_3") (pintype "passive"))
      (node (ref "R10G") (pin "2") (pinfunction "2_2") (pintype "passive"))
      (node (ref "RS10A") (pin "2") (pinfunction "2_2") (pintype "passive"))
    )
    (net (code "138") (name "Net-(D10B-PadA)") (class "Default")
      (node (ref "D10B") (pin "A") (pinfunction "A_A") (pintype "passive"))
      (node (ref "Q10B") (pin "1") (pinfunction "S_1") (pintype "passive"))
      (node (ref "Q10B") (pin "2") (pinfunction "S_2") (pintype "passive"))
      (node (ref "Q10B") (pin "3") (pinfunction "S_3") (pintype "passive"))
      (node (ref "R10H") (pin "1") (pinfunction "1_1") (pintype "passive"))
      (node (ref "RS10B") (pin "2") (pinfunction "2_2") (pintype "passive"))
    )
    (net (code "139") (name "Net-(D10B-PadK)") (class "Default")
      (node (ref "D10B") (pin "K") (pinfunction "K_K") (pintype "passive"))
      (node (ref "Q10B") (pin "5") (pinfunction "D_5") (pintype "passive"))
      (node (ref "Q10B") (pin "6") (pinfunction "D_6") (pintype "passive"))
      (node (ref "Q10B") (pin "7") (pinfunction "D_7") (pintype "passive"))
      (node (ref "Q10B") (pin "8") (pinfunction "D_8") (pintype "passive"))
      (node (ref "Q10B") (pin "9") (pinfunction "D_9") (pintype "passive"))
      (node (ref "R10B") (pin "1") (pinfunction "1_1") (pintype "passive"))
      (node (ref "T10") (pin "5") (pinfunction "5_5") (pintype "passive"))
    )
    (net (code "140") (name "Net-(D10D-PadC)") (class "Default")
      (node (ref "D10D") (pin "C") (pinfunction "C_C") (pintype "passive"))
      (node (ref "R10J") (pin "2") (pinfunction "2_2") (pintype "passive"))
    )
    (net (code "141") (name "Net-(D11-PadC)") (class "Default")
      (node (ref "D11") (pin "C") (pinfunction "C_C") (pintype "passive"))
      (node (ref "R55") (pin "1") (pinfunction "1_1") (pintype "passive"))
    )
    (net (code "142") (name "Net-(D11A-1)") (class "Default")
      (node (ref "D11A") (pin "2") (pinfunction "1_2") (pintype "passive"))
      (node (ref "Q11A") (pin "5") (pinfunction "5_5") (pintype "passive"))
      (node (ref "Q11A") (pin "6") (pinfunction "6_6") (pintype "passive"))
      (node (ref "Q11A") (pin "7") (pinfunction "7_7") (pintype "passive"))
      (node (ref "Q11A") (pin "8") (pinfunction "8_8") (pintype "passive"))
      (node (ref "Q11A") (pin "9") (pinfunction "8_9") (pintype "passive"))
      (node (ref "R11A") (pin "2") (pinfunction "2_2") (pintype "passive"))
      (node (ref "T11") (pin "10") (pinfunction "10_10") (pintype "passive"))
      (node (ref "T11") (pin "9") (pinfunction "9_9") (pintype "passive"))
    )
    (net (code "143") (name "Net-(D11A-2)") (class "Default")
      (node (ref "D11A") (pin "1") (pinfunction "2_1") (pintype "passive"))
      (node (ref "Q11A") (pin "1") (pinfunction "1_1") (pintype "passive"))
      (node (ref "Q11A") (pin "2") (pinfunction "2_2") (pintype "passive"))
      (node (ref "Q11A") (pin "3") (pinfunction "3_3") (pintype "passive"))
      (node (ref "R11G") (pin "2") (pinfunction "2_2") (pintype "passive"))
      (node (ref "RS11A") (pin "2") (pinfunction "2_2") (pintype "passive"))
    )
    (net (code "144") (name "Net-(D11B-PadA)") (class "Default")
      (node (ref "D11B") (pin "A") (pinfunction "A_A") (pintype "passive"))
      (node (ref "Q11B") (pin "1") (pinfunction "S_1") (pintype "passive"))
      (node (ref "Q11B") (pin "2") (pinfunction "S_2") (pintype "passive"))
      (node (ref "Q11B") (pin "3") (pinfunction "S_3") (pintype "passive"))
      (node (ref "R11H") (pin "1") (pinfunction "1_1") (pintype "passive"))
      (node (ref "RS11B") (pin "2") (pinfunction "2_2") (pintype "passive"))
    )
    (net (code "145") (name "Net-(D11B-PadK)") (class "Default")
      (node (ref "D11B") (pin "K") (pinfunction "K_K") (pintype "passive"))
      (node (ref "Q11B") (pin "5") (pinfunction "D_5") (pintype "passive"))
      (node (ref "Q11B") (pin "6") (pinfunction "D_6") (pintype "passive"))
      (node (ref "Q11B") (pin "7") (pinfunction "D_7") (pintype "passive"))
      (node (ref "Q11B") (pin "8") (pinfunction "D_8") (pintype "passive"))
      (node (ref "Q11B") (pin "9") (pinfunction "D_9") (pintype "passive"))
      (node (ref "R11B") (pin "1") (pinfunction "1_1") (pintype "passive"))
      (node (ref "T11") (pin "5") (pinfunction "5_5") (pintype "passive"))
    )
    (net (code "146") (name "Net-(D11D-PadC)") (class "Default")
      (node (ref "D11D") (pin "C") (pinfunction "C_C") (pintype "passive"))
      (node (ref "R11J") (pin "2") (pinfunction "2_2") (pintype "passive"))
    )
    (net (code "147") (name "Net-(D12-PadA)") (class "Default")
      (node (ref "D12") (pin "A") (pinfunction "A_A") (pintype "passive"))
      (node (ref "R58") (pin "2") (pinfunction "2_2") (pintype "passive"))
    )
    (net (code "148") (name "Net-(D12-PadC)") (class "Default")
      (node (ref "D12") (pin "C") (pinfunction "C_C") (pintype "passive"))
      (node (ref "Q6") (pin "2") (pinfunction "2_2") (pintype "passive"))
    )
    (net (code "149") (name "Net-(D12A-1)") (class "Default")
      (node (ref "D12A") (pin "2") (pinfunction "1_2") (pintype "passive"))
      (node (ref "Q12A") (pin "5") (pinfunction "5_5") (pintype "passive"))
      (node (ref "Q12A") (pin "6") (pinfunction "6_6") (pintype "passive"))
      (node (ref "Q12A") (pin "7") (pinfunction "7_7") (pintype "passive"))
      (node (ref "Q12A") (pin "8") (pinfunction "8_8") (pintype "passive"))
      (node (ref "Q12A") (pin "9") (pinfunction "8_9") (pintype "passive"))
      (node (ref "R12A") (pin "2") (pinfunction "2_2") (pintype "passive"))
      (node (ref "T12") (pin "10") (pinfunction "10_10") (pintype "passive"))
      (node (ref "T12") (pin "9") (pinfunction "9_9") (pintype "passive"))
    )
    (net (code "150") (name "Net-(D12A-2)") (class "Default")
      (node (ref "D12A") (pin "1") (pinfunction "2_1") (pintype "passive"))
      (node (ref "Q12A") (pin "1") (pinfunction "1_1") (pintype "passive"))
      (node (ref "Q12A") (pin "2") (pinfunction "2_2") (pintype "passive"))
      (node (ref "Q12A") (pin "3") (pinfunction "3_3") (pintype "passive"))
      (node (ref "R12G") (pin "2") (pinfunction "2_2") (pintype "passive"))
      (node (ref "RS12A") (pin "2") (pinfunction "2_2") (pintype "passive"))
    )
    (net (code "151") (name "Net-(D12B-PadA)") (class "Default")
      (node (ref "D12B") (pin "A") (pinfunction "A_A") (pintype "passive"))
      (node (ref "Q12B") (pin "1") (pinfunction "S_1") (pintype "passive"))
      (node (ref "Q12B") (pin "2") (pinfunction "S_2") (pintype "passive"))
      (node (ref "Q12B") (pin "3") (pinfunction "S_3") (pintype "passive"))
      (node (ref "R12H") (pin "1") (pinfunction "1_1") (pintype "passive"))
      (node (ref "RS12B") (pin "2") (pinfunction "2_2") (pintype "passive"))
    )
    (net (code "152") (name "Net-(D12B-PadK)") (class "Default")
      (node (ref "D12B") (pin "K") (pinfunction "K_K") (pintype "passive"))
      (node (ref "Q12B") (pin "5") (pinfunction "D_5") (pintype "passive"))
      (node (ref "Q12B") (pin "6") (pinfunction "D_6") (pintype "passive"))
      (node (ref "Q12B") (pin "7") (pinfunction "D_7") (pintype "passive"))
      (node (ref "Q12B") (pin "8") (pinfunction "D_8") (pintype "passive"))
      (node (ref "Q12B") (pin "9") (pinfunction "D_9") (pintype "passive"))
      (node (ref "R12B") (pin "1") (pinfunction "1_1") (pintype "passive"))
      (node (ref "T12") (pin "5") (pinfunction "5_5") (pintype "passive"))
    )
    (net (code "153") (name "Net-(D12D-PadC)") (class "Default")
      (node (ref "D12D") (pin "C") (pinfunction "C_C") (pintype "passive"))
      (node (ref "R12J") (pin "2") (pinfunction "2_2") (pintype "passive"))
    )
    (net (code "154") (name "Net-(D13-K)") (class "Default")
      (node (ref "D13") (pin "C") (pinfunction "K_C") (pintype "passive"))
      (node (ref "Q2") (pin "3") (pinfunction "D_3") (pintype "passive"))
      (node (ref "R8") (pin "2") (pinfunction "2_2") (pintype "passive"))
    )
    (net (code "155") (name "Net-(Q3A-Pad4)") (class "Default")
      (node (ref "Q3A") (pin "4") (pinfunction "4_4") (pintype "passive"))
      (node (ref "R3C") (pin "2") (pinfunction "2_2") (pintype "passive"))
    )
    (net (code "156") (name "Net-(Q3B-G)") (class "Default")
      (node (ref "Q3B") (pin "4") (pinfunction "G_4") (pintype "passive"))
      (node (ref "R3F") (pin "1") (pinfunction "1_1") (pintype "passive"))
    )
    (net (code "157") (name "Net-(Q4-C)") (class "Default")
      (node (ref "D10") (pin "A") (pinfunction "A_A") (pintype "passive"))
      (node (ref "Q4") (pin "3") (pinfunction "C_3") (pintype "passive"))
    )
    (net (code "158") (name "Net-(Q4-E)") (class "Default")
      (node (ref "D8") (pin "A") (pinfunction "A_A") (pintype "passive"))
      (node (ref "Q4") (pin "2") (pinfunction "E_2") (pintype "passive"))
    )
    (net (code "159") (name "Net-(Q4A-Pad4)") (class "Default")
      (node (ref "Q4A") (pin "4") (pinfunction "4_4") (pintype "passive"))
      (node (ref "R4C") (pin "2") (pinfunction "2_2") (pintype "passive"))
    )
    (net (code "160") (name "Net-(Q4B-G)") (class "Default")
      (node (ref "Q4B") (pin "4") (pinfunction "G_4") (pintype "passive"))
      (node (ref "R4F") (pin "1") (pinfunction "1_1") (pintype "passive"))
    )
    (net (code "161") (name "Net-(Q5-D)") (class "Default")
      (node (ref "D13") (pin "A") (pinfunction "A_A") (pintype "passive"))
      (node (ref "Q5") (pin "3") (pinfunction "D_3") (pintype "passive"))
    )
    (net (code "162") (name "Net-(Q5-G)") (class "Default")
      (node (ref "Q5") (pin "1") (pinfunction "G_1") (pintype "passive"))
      (node (ref "Q6") (pin "3") (pinfunction "3_3") (pintype "passive"))
      (node (ref "R53") (pin "2") (pinfunction "2_2") (pintype "passive"))
    )
    (net (code "163") (name "Net-(Q5A-Pad4)") (class "Default")
      (node (ref "Q5A") (pin "4") (pinfunction "4_4") (pintype "passive"))
      (node (ref "R5C") (pin "2") (pinfunction "2_2") (pintype "passive"))
    )
    (net (code "164") (name "Net-(Q5B-G)") (class "Default")
      (node (ref "Q5B") (pin "4") (pinfunction "G_4") (pintype "passive"))
      (node (ref "R5F") (pin "1") (pinfunction "1_1") (pintype "passive"))
    )
    (net (code "165") (name "Net-(Q6A-Pad4)") (class "Default")
      (node (ref "Q6A") (pin "4") (pinfunction "4_4") (pintype "passive"))
      (node (ref "R6C") (pin "2") (pinfunction "2_2") (pintype "passive"))
    )
    (net (code "166") (name "Net-(Q6B-G)") (class "Default")
      (node (ref "Q6B") (pin "4") (pinfunction "G_4") (pintype "passive"))
      (node (ref "R6F") (pin "1") (pinfunction "1_1") (pintype "passive"))
    )
    (net (code "167") (name "Net-(Q9A-Pad4)") (class "Default")
      (node (ref "Q9A") (pin "4") (pinfunction "4_4") (pintype "passive"))
      (node (ref "R9C") (pin "2") (pinfunction "2_2") (pintype "passive"))
    )
    (net (code "168") (name "Net-(Q9B-G)") (class "Default")
      (node (ref "Q9B") (pin "4") (pinfunction "G_4") (pintype "passive"))
      (node (ref "R9F") (pin "1") (pinfunction "1_1") (pintype "passive"))
    )
    (net (code "169") (name "Net-(Q10A-Pad4)") (class "Default")
      (node (ref "Q10A") (pin "4") (pinfunction "4_4") (pintype "passive"))
      (node (ref "R10C") (pin "2") (pinfunction "2_2") (pintype "passive"))
    )
    (net (code "170") (name "Net-(Q10B-G)") (class "Default")
      (node (ref "Q10B") (pin "4") (pinfunction "G_4") (pintype "passive"))
      (node (ref "R10F") (pin "1") (pinfunction "1_1") (pintype "passive"))
    )
    (net (code "171") (name "Net-(Q11A-Pad4)") (class "Default")
      (node (ref "Q11A") (pin "4") (pinfunction "4_4") (pintype "passive"))
      (node (ref "R11C") (pin "2") (pinfunction "2_2") (pintype "passive"))
    )
    (net (code "172") (name "Net-(Q11B-G)") (class "Default")
      (node (ref "Q11B") (pin "4") (pinfunction "G_4") (pintype "passive"))
      (node (ref "R11F") (pin "1") (pinfunction "1_1") (pintype "passive"))
    )
    (net (code "173") (name "Net-(Q12A-Pad4)") (class "Default")
      (node (ref "Q12A") (pin "4") (pinfunction "4_4") (pintype "passive"))
      (node (ref "R12C") (pin "2") (pinfunction "2_2") (pintype "passive"))
    )
    (net (code "174") (name "Net-(Q12B-G)") (class "Default")
      (node (ref "Q12B") (pin "4") (pinfunction "G_4") (pintype "passive"))
      (node (ref "R12F") (pin "1") (pinfunction "1_1") (pintype "passive"))
    )
    (net (code "175") (name "Net-(R21-Pad2)") (class "Default")
      (node (ref "R21") (pin "2") (pinfunction "2_2") (pintype "passive"))
      (node (ref "R24") (pin "1") (pinfunction "1_1") (pintype "passive"))
    )
    (net (code "176") (name "Net-(T3-Pad4)") (class "Default")
      (node (ref "T3") (pin "4") (pinfunction "4_4") (pintype "passive"))
      (node (ref "T3") (pin "6") (pinfunction "6_6") (pintype "passive"))
    )
    (net (code "177") (name "Net-(T4-Pad4)") (class "Default")
      (node (ref "T4") (pin "4") (pinfunction "4_4") (pintype "passive"))
      (node (ref "T4") (pin "6") (pinfunction "6_6") (pintype "passive"))
    )
    (net (code "178") (name "Net-(T5-Pad4)") (class "Default")
      (node (ref "T5") (pin "4") (pinfunction "4_4") (pintype "passive"))
      (node (ref "T5") (pin "6") (pinfunction "6_6") (pintype "passive"))
    )
    (net (code "179") (name "Net-(T6-Pad4)") (class "Default")
      (node (ref "T6") (pin "4") (pinfunction "4_4") (pintype "passive"))
      (node (ref "T6") (pin "6") (pinfunction "6_6") (pintype "passive"))
    )
    (net (code "180") (name "Net-(T9-Pad4)") (class "Default")
      (node (ref "T9") (pin "4") (pinfunction "4_4") (pintype "passive"))
      (node (ref "T9") (pin "6") (pinfunction "6_6") (pintype "passive"))
    )
    (net (code "181") (name "Net-(T10-Pad4)") (class "Default")
      (node (ref "T10") (pin "4") (pinfunction "4_4") (pintype "passive"))
      (node (ref "T10") (pin "6") (pinfunction "6_6") (pintype "passive"))
    )
    (net (code "182") (name "Net-(T11-Pad4)") (class "Default")
      (node (ref "T11") (pin "4") (pinfunction "4_4") (pintype "passive"))
      (node (ref "T11") (pin "6") (pinfunction "6_6") (pintype "passive"))
    )
    (net (code "183") (name "Net-(T12-Pad4)") (class "Default")
      (node (ref "T12") (pin "4") (pinfunction "4_4") (pintype "passive"))
      (node (ref "T12") (pin "6") (pinfunction "6_6") (pintype "passive"))
    )
    (net (code "184") (name "Net-(U2-BOOST-)") (class "Default")
      (node (ref "C7") (pin "1") (pinfunction "1_1") (pintype "passive"))
      (node (ref "U2") (pin "41") (pinfunction "BOOST-_41") (pintype "power_in"))
    )
    (net (code "185") (name "Net-(U2-CSBI)") (class "Default")
      (node (ref "D5") (pin "A") (pinfunction "A_A") (pintype "passive"))
      (node (ref "U2") (pin "16") (pinfunction "CSBI_16") (pintype "input"))
    )
    (net (code "186") (name "Net-(U2-RTONP)") (class "Default")
      (node (ref "R22") (pin "1") (pinfunction "1_1") (pintype "passive"))
      (node (ref "U2") (pin "14") (pinfunction "RTONP_14") (pintype "passive"))
    )
    (net (code "187") (name "Net-(U2-RTONS)") (class "Default")
      (node (ref "R21") (pin "1") (pinfunction "1_1") (pintype "passive"))
      (node (ref "U2") (pin "13") (pinfunction "RTONS_13") (pintype "passive"))
    )
    (net (code "188") (name "Net-(U2-SCKI)") (class "Default")
      (node (ref "D6") (pin "A") (pinfunction "A_A") (pintype "passive"))
      (node (ref "U2") (pin "17") (pinfunction "SCKI_17") (pintype "input"))
    )
    (net (code "189") (name "Net-(U2-SDI)") (class "Default")
      (node (ref "D7") (pin "A") (pinfunction "A_A") (pintype "passive"))
      (node (ref "U2") (pin "18") (pinfunction "SDI_18") (pintype "input"))
    )
    (net (code "190") (name "unconnected-(U2-SDO-Pad19)") (class "Default")
      (node (ref "U2") (pin "19") (pinfunction "SDO_19") (pintype "output"))
    )
  )
)
